# 88.net
KiCad netlist of a schematic drawn in Altium Designer
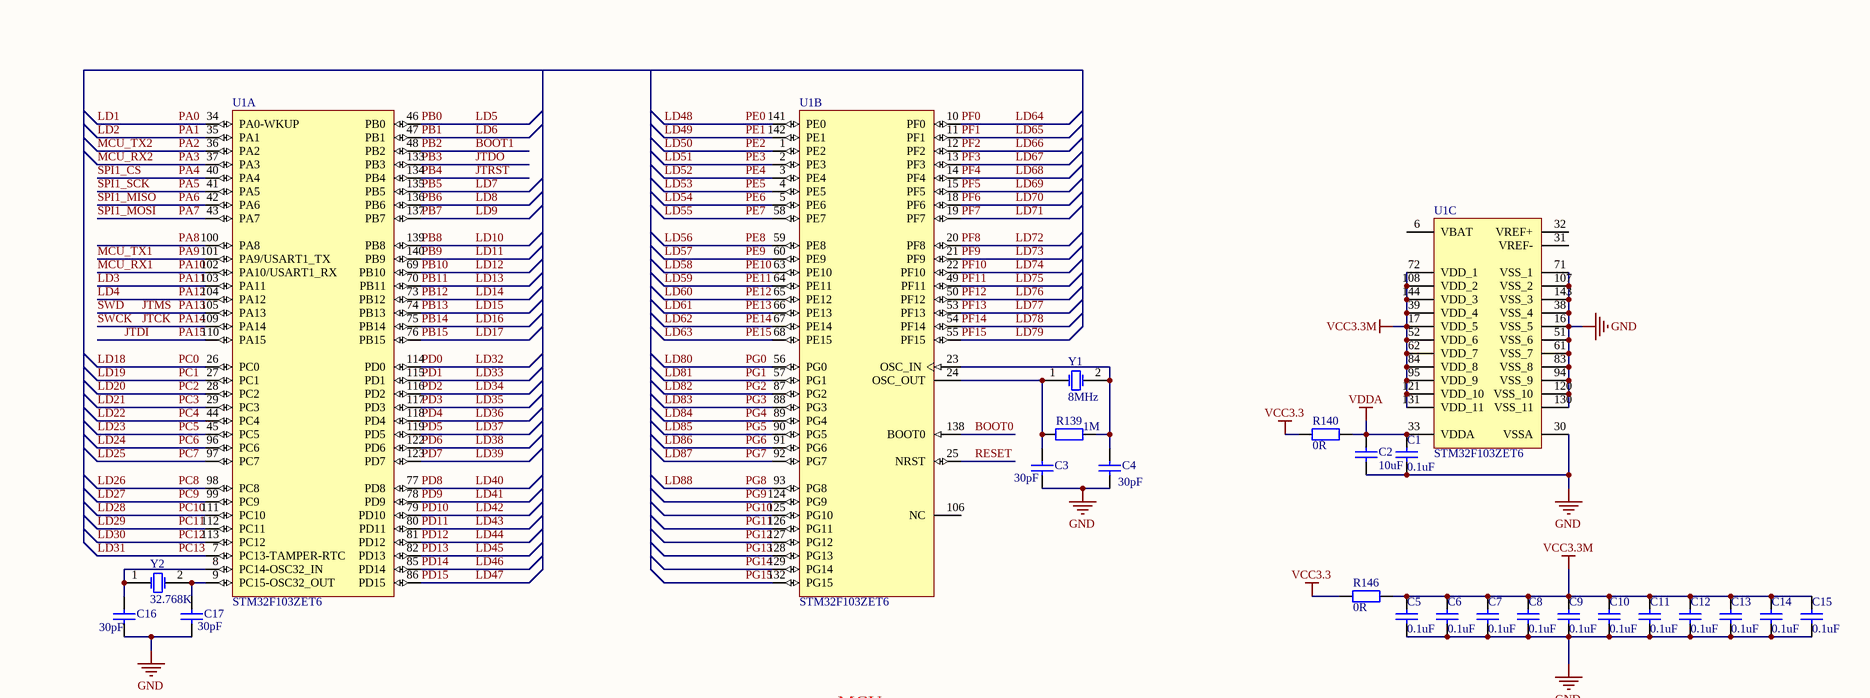
[diagram p0: 88路激光器工程.SchDoc, top left]
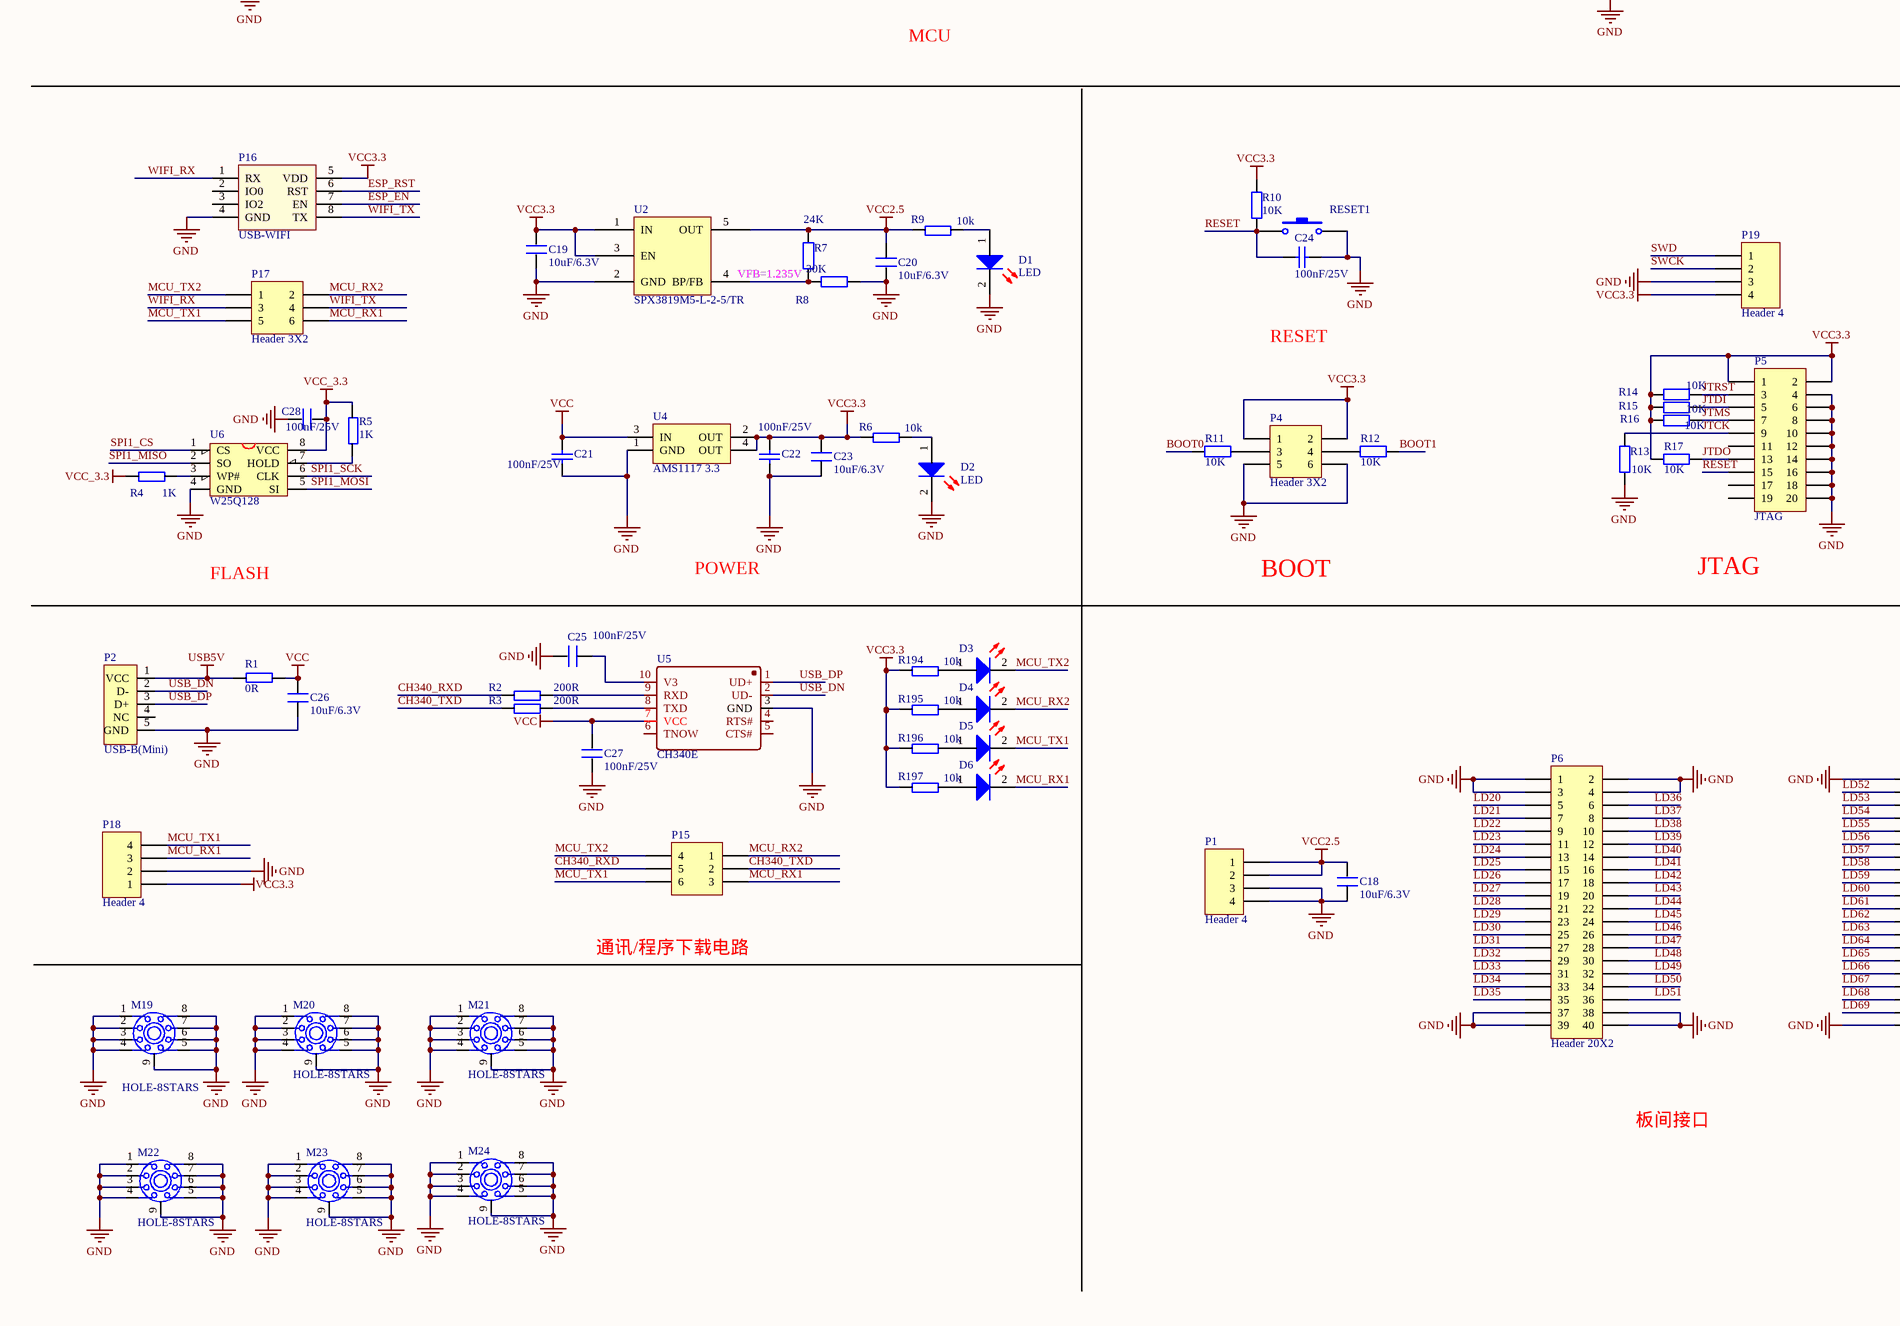
[diagram p1: 88路激光器工程.SchDoc, bottom left]
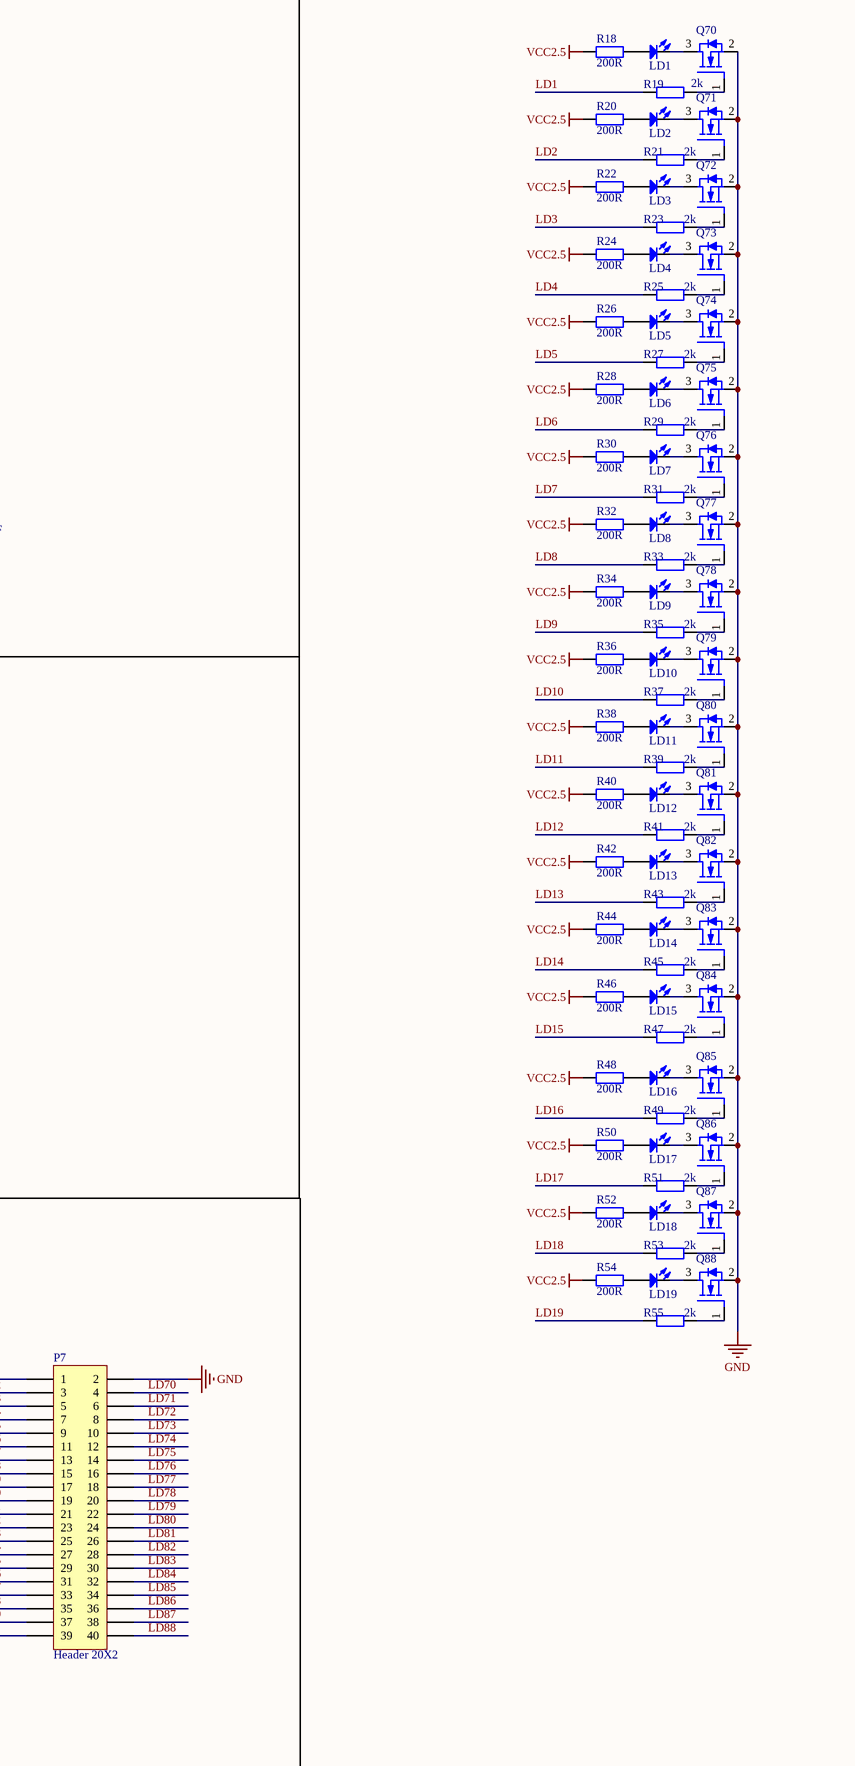
[diagram p2: 88路激光器工程.SchDoc, bottom right]

(export (version "E")
  (design (tool "Eeschema 10.0.6"))
  (components
    (comp (ref "C1")
      (value "0.1uF")
      (footprint "C0805")
      (description "Capacitor")
      (fields (field (name "PUBLISHER") "Altium Limited"))
      (libsource (lib "Miscellaneous Devices") (part "Cap"))
    )
    (comp (ref "C2")
      (value "10uF")
      (footprint "C0805")
      (description "Capacitor")
      (fields (field (name "PUBLISHER") "Altium Limited"))
      (libsource (lib "Miscellaneous Devices") (part "Cap"))
    )
    (comp (ref "C3")
      (value "30pF")
      (footprint "C0805")
      (description "Capacitor")
      (fields (field (name "PUBLISHER") "Altium Limited"))
      (libsource (lib "Miscellaneous Devices") (part "Cap"))
    )
    (comp (ref "C4")
      (value "30pF")
      (footprint "C0805")
      (description "Capacitor")
      (fields (field (name "PUBLISHER") "Altium Limited"))
      (libsource (lib "Miscellaneous Devices") (part "Cap"))
    )
    (comp (ref "C5")
      (value "0.1uF")
      (footprint "C0805")
      (description "Capacitor")
      (fields (field (name "PUBLISHER") "Altium Limited"))
      (libsource (lib "Miscellaneous Devices") (part "Cap"))
    )
    (comp (ref "C6")
      (value "0.1uF")
      (footprint "C0805")
      (description "Capacitor")
      (fields (field (name "PUBLISHER") "Altium Limited"))
      (libsource (lib "Miscellaneous Devices") (part "Cap"))
    )
    (comp (ref "C7")
      (value "0.1uF")
      (footprint "C0805")
      (description "Capacitor")
      (fields (field (name "PUBLISHER") "Altium Limited"))
      (libsource (lib "Miscellaneous Devices") (part "Cap"))
    )
    (comp (ref "C8")
      (value "0.1uF")
      (footprint "C0805")
      (description "Capacitor")
      (fields (field (name "PUBLISHER") "Altium Limited"))
      (libsource (lib "Miscellaneous Devices") (part "Cap"))
    )
    (comp (ref "C9")
      (value "0.1uF")
      (footprint "C0805")
      (description "Capacitor")
      (fields (field (name "PUBLISHER") "Altium Limited"))
      (libsource (lib "Miscellaneous Devices") (part "Cap"))
    )
    (comp (ref "C10")
      (value "0.1uF")
      (footprint "C0805")
      (description "Capacitor")
      (fields (field (name "PUBLISHER") "Altium Limited"))
      (libsource (lib "Miscellaneous Devices") (part "Cap"))
    )
    (comp (ref "C11")
      (value "0.1uF")
      (footprint "C0805")
      (description "Capacitor")
      (fields (field (name "PUBLISHER") "Altium Limited"))
      (libsource (lib "Miscellaneous Devices") (part "Cap"))
    )
    (comp (ref "C12")
      (value "0.1uF")
      (footprint "C0805")
      (description "Capacitor")
      (fields (field (name "PUBLISHER") "Altium Limited"))
      (libsource (lib "Miscellaneous Devices") (part "Cap"))
    )
    (comp (ref "C13")
      (value "0.1uF")
      (footprint "C0805")
      (description "Capacitor")
      (fields (field (name "PUBLISHER") "Altium Limited"))
      (libsource (lib "Miscellaneous Devices") (part "Cap"))
    )
    (comp (ref "C14")
      (value "0.1uF")
      (footprint "C0805")
      (description "Capacitor")
      (fields (field (name "PUBLISHER") "Altium Limited"))
      (libsource (lib "Miscellaneous Devices") (part "Cap"))
    )
    (comp (ref "C15")
      (value "0.1uF")
      (footprint "C0805")
      (description "Capacitor")
      (fields (field (name "PUBLISHER") "Altium Limited"))
      (libsource (lib "Miscellaneous Devices") (part "Cap"))
    )
    (comp (ref "C16")
      (value "30pF")
      (footprint "C0805")
      (description "Capacitor")
      (fields (field (name "PUBLISHER") "Altium Limited"))
      (libsource (lib "Miscellaneous Devices") (part "Cap"))
    )
    (comp (ref "C17")
      (value "30pF")
      (footprint "C0805")
      (description "Capacitor")
      (fields (field (name "PUBLISHER") "Altium Limited"))
      (libsource (lib "Miscellaneous Devices") (part "Cap"))
    )
    (comp (ref "C18")
      (value "10uF/6.3V")
      (footprint "C0805")
      (libsource (lib "Explorer STM32F407封装库2") (part "C"))
    )
    (comp (ref "C19")
      (value "10uF/6.3V")
      (footprint "C0805")
      (libsource (lib "Explorer STM32F407封装库2") (part "C"))
    )
    (comp (ref "C20")
      (value "10uF/6.3V")
      (footprint "C0805")
      (libsource (lib "Explorer STM32F407封装库2") (part "C"))
    )
    (comp (ref "C21")
      (value "100nF/25V")
      (footprint "C0805")
      (description "Capacitor")
      (fields (field (name "PUBLISHER") "Altium Limited"))
      (libsource (lib "Miscellaneous Devices") (part "Cap"))
    )
    (comp (ref "C22")
      (value "100nF/25V")
      (footprint "C0805")
      (description "Capacitor")
      (fields (field (name "PUBLISHER") "Altium Limited"))
      (libsource (lib "Miscellaneous Devices") (part "Cap"))
    )
    (comp (ref "C23")
      (value "10uF/6.3V")
      (footprint "C0805")
      (libsource (lib "Explorer STM32F407封装库2") (part "C"))
    )
    (comp (ref "C24")
      (value "100nF/25V")
      (footprint "C0805")
      (description "Capacitor")
      (fields (field (name "PUBLISHER") "Altium Limited"))
      (libsource (lib "Miscellaneous Devices") (part "Cap"))
    )
    (comp (ref "C25")
      (value "100nF/25V")
      (footprint "C0805")
      (libsource (lib "Explorer STM32F407封装库2") (part "C"))
    )
    (comp (ref "C26")
      (value "10uF/6.3V")
      (footprint "C0805")
      (libsource (lib "Explorer STM32F407封装库2") (part "C"))
    )
    (comp (ref "C27")
      (value "100nF/25V")
      (footprint "C0805")
      (libsource (lib "Explorer STM32F407封装库2") (part "C"))
    )
    (comp (ref "C28")
      (value "100nF/25V")
      (footprint "C0805")
      (libsource (lib "Explorer STM32F407封装库2") (part "C"))
    )
    (comp (ref "D1")
      (value "LED")
      (footprint "LED_0805")
      (description "0603 无色透明 λp=940nm VR=5V VF(typ)=1.2V IF=65mA PD=130mW")
      (libsource (lib "TOF_SCH") (part "LED_IR"))
    )
    (comp (ref "D2")
      (value "LED")
      (footprint "LED_0805")
      (description "0603 无色透明 λp=940nm VR=5V VF(typ)=1.2V IF=65mA PD=130mW")
      (libsource (lib "TOF_SCH") (part "LED_IR"))
    )
    (comp (ref "D3")
      (value "LED")
      (footprint "LED_0805")
      (description "0603 无色透明 λp=940nm VR=5V VF(typ)=1.2V IF=65mA PD=130mW")
      (libsource (lib "TOF_SCH") (part "LED_IR"))
    )
    (comp (ref "D4")
      (value "LED")
      (footprint "LED_0805")
      (description "0603 无色透明 λp=940nm VR=5V VF(typ)=1.2V IF=65mA PD=130mW")
      (libsource (lib "TOF_SCH") (part "LED_IR"))
    )
    (comp (ref "D5")
      (value "LED")
      (footprint "LED_0805")
      (description "0603 无色透明 λp=940nm VR=5V VF(typ)=1.2V IF=65mA PD=130mW")
      (libsource (lib "TOF_SCH") (part "LED_IR"))
    )
    (comp (ref "D6")
      (value "LED")
      (footprint "LED_0805")
      (description "0603 无色透明 λp=940nm VR=5V VF(typ)=1.2V IF=65mA PD=130mW")
      (libsource (lib "TOF_SCH") (part "LED_IR"))
    )
    (comp (ref "LD1") (value "LD") (footprint "LD_3P") (libsource (lib "SchLib1") (part "LD")))
    (comp (ref "LD2") (value "LD") (footprint "LD_3P") (libsource (lib "SchLib1") (part "LD")))
    (comp (ref "LD3") (value "LD") (footprint "LD_3P") (libsource (lib "SchLib1") (part "LD")))
    (comp (ref "LD4") (value "LD") (footprint "LD_3P") (libsource (lib "SchLib1") (part "LD")))
    (comp (ref "LD5") (value "LD") (footprint "LD_3P") (libsource (lib "SchLib1") (part "LD")))
    (comp (ref "LD6") (value "LD") (footprint "LD_3P") (libsource (lib "SchLib1") (part "LD")))
    (comp (ref "LD7") (value "LD") (footprint "LD_3P") (libsource (lib "SchLib1") (part "LD")))
    (comp (ref "LD8") (value "LD") (footprint "LD_3P") (libsource (lib "SchLib1") (part "LD")))
    (comp (ref "LD9") (value "LD") (footprint "LD_3P") (libsource (lib "SchLib1") (part "LD")))
    (comp (ref "LD10") (value "LD") (footprint "LD_3P") (libsource (lib "SchLib1") (part "LD")))
    (comp (ref "LD11") (value "LD") (footprint "LD_3P") (libsource (lib "SchLib1") (part "LD")))
    (comp (ref "LD12") (value "LD") (footprint "LD_3P") (libsource (lib "SchLib1") (part "LD")))
    (comp (ref "LD13") (value "LD") (footprint "LD_3P") (libsource (lib "SchLib1") (part "LD")))
    (comp (ref "LD14") (value "LD") (footprint "LD_3P") (libsource (lib "SchLib1") (part "LD")))
    (comp (ref "LD15") (value "LD") (footprint "LD_3P") (libsource (lib "SchLib1") (part "LD")))
    (comp (ref "LD16") (value "LD") (footprint "LD_3P") (libsource (lib "SchLib1") (part "LD")))
    (comp (ref "LD17") (value "LD") (footprint "LD_3P") (libsource (lib "SchLib1") (part "LD")))
    (comp (ref "LD18") (value "LD") (footprint "LD_3P") (libsource (lib "SchLib1") (part "LD")))
    (comp (ref "LD19") (value "LD") (footprint "LD_3P") (libsource (lib "SchLib1") (part "LD")))
    (comp (ref "M19")
      (value "HOLE-8STARS")
      (footprint "HOLE_3MM")
      (libsource (lib "TOF_SCH") (part "HOLE-8STARS"))
    )
    (comp (ref "M20")
      (value "HOLE-8STARS")
      (footprint "HOLE_3MM")
      (libsource (lib "TOF_SCH") (part "HOLE-8STARS"))
    )
    (comp (ref "M21")
      (value "HOLE-8STARS")
      (footprint "HOLE_3MM")
      (libsource (lib "TOF_SCH") (part "HOLE-8STARS"))
    )
    (comp (ref "M22")
      (value "HOLE-8STARS")
      (footprint "HOLE_3MM")
      (libsource (lib "TOF_SCH") (part "HOLE-8STARS"))
    )
    (comp (ref "M23")
      (value "HOLE-8STARS")
      (footprint "HOLE_3MM")
      (libsource (lib "TOF_SCH") (part "HOLE-8STARS"))
    )
    (comp (ref "M24")
      (value "HOLE-8STARS")
      (footprint "HOLE_3MM")
      (libsource (lib "TOF_SCH") (part "HOLE-8STARS"))
    )
    (comp (ref "P1")
      (value "Header 4")
      (footprint "XH2.54MM_4P_立式")
      (description "Header, 4-Pin")
      (fields (field (name "PUBLISHER") "Altium Limited"))
      (libsource (lib "") (part "Header 4_2"))
    )
    (comp (ref "P2")
      (value "USB-B(Mini)")
      (footprint "MICRO_USB5P_带牛角")
      (libsource (lib "阿波罗STM32F4&F7底板封装库") (part "USB5"))
    )
    (comp (ref "P4")
      (value "Header 3X2")
      (footprint "HDR2X3")
      (description "Header, 3-Pin, Dual row")
      (fields (field (name "PUBLISHER") "Altium Limited"))
      (libsource (lib "Miscellaneous Connectors") (part "Header 3X2"))
    )
    (comp (ref "P5")
      (value "JTAG")
      (footprint "JTAG_2X10P_2.54MM")
      (description "Header, 10-Pin, Dual row")
      (fields (field (name "PUBLISHER") "Altium Limited"))
      (libsource (lib "Miscellaneous Connectors") (part "Header 10X2"))
    )
    (comp (ref "P6")
      (value "Header 20X2")
      (footprint "JATG_2.0mm_2x20P_SMD")
      (description "Header, 20-Pin, Dual row")
      (fields (field (name "PUBLISHER") "Altium Limited"))
      (libsource (lib "Miscellaneous Connectors") (part "Header 20X2"))
    )
    (comp (ref "P7")
      (value "Header 20X2")
      (footprint "JATG_2.0mm_2x20P_SMD")
      (description "Header, 20-Pin, Dual row")
      (fields (field (name "PUBLISHER") "Altium Limited"))
      (libsource (lib "Miscellaneous Connectors") (part "Header 20X2"))
    )
    (comp (ref "P15")
      (value "Header 3X2A")
      (footprint "HDR2X3_CEN")
      (description "Header, 3-Pin, Dual row")
      (fields (field (name "PUBLISHER") "Altium Limited"))
      (libsource (lib "Miscellaneous Connectors") (part "Header 3X2A"))
    )
    (comp (ref "P16")
      (value "USB-WIFI")
      (footprint "UART-WIFI")
      (libsource (lib "Schlib1") (part "USB-WIFI"))
    )
    (comp (ref "P17")
      (value "Header 3X2")
      (footprint "HDR2X3")
      (description "Header, 3-Pin, Dual row")
      (fields (field (name "PUBLISHER") "Altium Limited"))
      (libsource (lib "Miscellaneous Connectors") (part "Header 3X2"))
    )
    (comp (ref "P18")
      (value "Header 4")
      (footprint "HDR1X4")
      (description "Header, 4-Pin")
      (fields (field (name "PUBLISHER") "Altium Limited"))
      (libsource (lib "") (part "Header 4_1"))
    )
    (comp (ref "P19")
      (value "Header 4")
      (footprint "HDR1X4")
      (description "Header, 4-Pin")
      (fields (field (name "PUBLISHER") "Altium Limited"))
      (libsource (lib "Miscellaneous Connectors") (part "Header 4"))
    )
    (comp (ref "Q70") (value "NMOS") (footprint "SOT23-3") (libsource (lib "88路激光器工程") (part "NMOS")))
    (comp (ref "Q71") (value "NMOS") (footprint "SOT23-3") (libsource (lib "88路激光器工程") (part "NMOS")))
    (comp (ref "Q72") (value "NMOS") (footprint "SOT23-3") (libsource (lib "88路激光器工程") (part "NMOS")))
    (comp (ref "Q73") (value "NMOS") (footprint "SOT23-3") (libsource (lib "88路激光器工程") (part "NMOS")))
    (comp (ref "Q74") (value "NMOS") (footprint "SOT23-3") (libsource (lib "88路激光器工程") (part "NMOS")))
    (comp (ref "Q75") (value "NMOS") (footprint "SOT23-3") (libsource (lib "88路激光器工程") (part "NMOS")))
    (comp (ref "Q76") (value "NMOS") (footprint "SOT23-3") (libsource (lib "88路激光器工程") (part "NMOS")))
    (comp (ref "Q77") (value "NMOS") (footprint "SOT23-3") (libsource (lib "88路激光器工程") (part "NMOS")))
    (comp (ref "Q78") (value "NMOS") (footprint "SOT23-3") (libsource (lib "88路激光器工程") (part "NMOS")))
    (comp (ref "Q79") (value "NMOS") (footprint "SOT23-3") (libsource (lib "88路激光器工程") (part "NMOS")))
    (comp (ref "Q80") (value "NMOS") (footprint "SOT23-3") (libsource (lib "88路激光器工程") (part "NMOS")))
    (comp (ref "Q81") (value "NMOS") (footprint "SOT23-3") (libsource (lib "88路激光器工程") (part "NMOS")))
    (comp (ref "Q82") (value "NMOS") (footprint "SOT23-3") (libsource (lib "88路激光器工程") (part "NMOS")))
    (comp (ref "Q83") (value "NMOS") (footprint "SOT23-3") (libsource (lib "88路激光器工程") (part "NMOS")))
    (comp (ref "Q84") (value "NMOS") (footprint "SOT23-3") (libsource (lib "88路激光器工程") (part "NMOS")))
    (comp (ref "Q85") (value "NMOS") (footprint "SOT23-3") (libsource (lib "88路激光器工程") (part "NMOS")))
    (comp (ref "Q86") (value "NMOS") (footprint "SOT23-3") (libsource (lib "88路激光器工程") (part "NMOS")))
    (comp (ref "Q87") (value "NMOS") (footprint "SOT23-3") (libsource (lib "88路激光器工程") (part "NMOS")))
    (comp (ref "Q88") (value "NMOS") (footprint "SOT23-3") (libsource (lib "88路激光器工程") (part "NMOS")))
    (comp (ref "R1") (value "0R") (footprint "R0805") (libsource (lib "Explorer STM32F407封装库2") (part "R")))
    (comp (ref "R2") (value "200R") (footprint "R0805") (libsource (lib "Explorer STM32F407封装库2") (part "R")))
    (comp (ref "R3") (value "200R") (footprint "R0805") (libsource (lib "Explorer STM32F407封装库2") (part "R")))
    (comp (ref "R4") (value "1K") (footprint "R0805") (libsource (lib "Explorer STM32F407封装库2") (part "R")))
    (comp (ref "R5") (value "1K") (footprint "R0805") (libsource (lib "Explorer STM32F407封装库2") (part "R")))
    (comp (ref "R6") (value "10k") (footprint "R0805") (libsource (lib "Explorer STM32F407封装库2") (part "R")))
    (comp (ref "R7")
      (value "24K")
      (footprint "R0805")
      (description "Resistor")
      (fields (field (name "PUBLISHER") "Altium Limited"))
      (libsource (lib "") (part "Res2_2"))
    )
    (comp (ref "R8")
      (value "30K")
      (footprint "R0805")
      (description "Resistor")
      (fields (field (name "PUBLISHER") "Altium Limited"))
      (libsource (lib "Miscellaneous Devices") (part "Res2"))
    )
    (comp (ref "R9") (value "10k") (footprint "R0805") (libsource (lib "Explorer STM32F407封装库2") (part "R")))
    (comp (ref "R10")
      (value "10K")
      (footprint "R0805")
      (description "Resistor")
      (fields (field (name "PUBLISHER") "Altium Limited"))
      (libsource (lib "") (part "Res2_2"))
    )
    (comp (ref "R11")
      (value "10K")
      (footprint "R0805")
      (description "Resistor")
      (fields (field (name "PUBLISHER") "Altium Limited"))
      (libsource (lib "") (part "Res2_1"))
    )
    (comp (ref "R12")
      (value "10K")
      (footprint "R0805")
      (description "Resistor")
      (fields (field (name "PUBLISHER") "Altium Limited"))
      (libsource (lib "") (part "Res2_1"))
    )
    (comp (ref "R13")
      (value "10K")
      (footprint "R0805")
      (description "Resistor")
      (fields (field (name "PUBLISHER") "Altium Limited"))
      (libsource (lib "") (part "Res2_2"))
    )
    (comp (ref "R14")
      (value "10K")
      (footprint "R0805")
      (description "Resistor")
      (fields (field (name "PUBLISHER") "Altium Limited"))
      (libsource (lib "") (part "Res2_1"))
    )
    (comp (ref "R15")
      (value "10K")
      (footprint "R0805")
      (description "Resistor")
      (fields (field (name "PUBLISHER") "Altium Limited"))
      (libsource (lib "") (part "Res2_1"))
    )
    (comp (ref "R16")
      (value "10K")
      (footprint "R0805")
      (description "Resistor")
      (fields (field (name "PUBLISHER") "Altium Limited"))
      (libsource (lib "") (part "Res2_1"))
    )
    (comp (ref "R17")
      (value "10K")
      (footprint "R0805")
      (description "Resistor")
      (fields (field (name "PUBLISHER") "Altium Limited"))
      (libsource (lib "") (part "Res2_1"))
    )
    (comp (ref "R18")
      (value "200R")
      (footprint "R0805")
      (description "Resistor")
      (fields (field (name "PUBLISHER") "Altium Limited"))
      (libsource (lib "Miscellaneous Devices") (part "Res2"))
    )
    (comp (ref "R19")
      (value "2k")
      (footprint "R0805")
      (description "Resistor")
      (fields (field (name "PUBLISHER") "Altium Limited"))
      (libsource (lib "Miscellaneous Devices") (part "Res2"))
    )
    (comp (ref "R20")
      (value "200R")
      (footprint "R0805")
      (description "Resistor")
      (fields (field (name "PUBLISHER") "Altium Limited"))
      (libsource (lib "Miscellaneous Devices") (part "Res2"))
    )
    (comp (ref "R21")
      (value "2k")
      (footprint "R0805")
      (description "Resistor")
      (fields (field (name "PUBLISHER") "Altium Limited"))
      (libsource (lib "Miscellaneous Devices") (part "Res2"))
    )
    (comp (ref "R22")
      (value "200R")
      (footprint "R0805")
      (description "Resistor")
      (fields (field (name "PUBLISHER") "Altium Limited"))
      (libsource (lib "Miscellaneous Devices") (part "Res2"))
    )
    (comp (ref "R23")
      (value "2k")
      (footprint "R0805")
      (description "Resistor")
      (fields (field (name "PUBLISHER") "Altium Limited"))
      (libsource (lib "Miscellaneous Devices") (part "Res2"))
    )
    (comp (ref "R24")
      (value "200R")
      (footprint "R0805")
      (description "Resistor")
      (fields (field (name "PUBLISHER") "Altium Limited"))
      (libsource (lib "Miscellaneous Devices") (part "Res2"))
    )
    (comp (ref "R25")
      (value "2k")
      (footprint "R0805")
      (description "Resistor")
      (fields (field (name "PUBLISHER") "Altium Limited"))
      (libsource (lib "Miscellaneous Devices") (part "Res2"))
    )
    (comp (ref "R26")
      (value "200R")
      (footprint "R0805")
      (description "Resistor")
      (fields (field (name "PUBLISHER") "Altium Limited"))
      (libsource (lib "Miscellaneous Devices") (part "Res2"))
    )
    (comp (ref "R27")
      (value "2k")
      (footprint "R0805")
      (description "Resistor")
      (fields (field (name "PUBLISHER") "Altium Limited"))
      (libsource (lib "Miscellaneous Devices") (part "Res2"))
    )
    (comp (ref "R28")
      (value "200R")
      (footprint "R0805")
      (description "Resistor")
      (fields (field (name "PUBLISHER") "Altium Limited"))
      (libsource (lib "Miscellaneous Devices") (part "Res2"))
    )
    (comp (ref "R29")
      (value "2k")
      (footprint "R0805")
      (description "Resistor")
      (fields (field (name "PUBLISHER") "Altium Limited"))
      (libsource (lib "Miscellaneous Devices") (part "Res2"))
    )
    (comp (ref "R30")
      (value "200R")
      (footprint "R0805")
      (description "Resistor")
      (fields (field (name "PUBLISHER") "Altium Limited"))
      (libsource (lib "Miscellaneous Devices") (part "Res2"))
    )
    (comp (ref "R31")
      (value "2k")
      (footprint "R0805")
      (description "Resistor")
      (fields (field (name "PUBLISHER") "Altium Limited"))
      (libsource (lib "Miscellaneous Devices") (part "Res2"))
    )
    (comp (ref "R32")
      (value "200R")
      (footprint "R0805")
      (description "Resistor")
      (fields (field (name "PUBLISHER") "Altium Limited"))
      (libsource (lib "Miscellaneous Devices") (part "Res2"))
    )
    (comp (ref "R33")
      (value "2k")
      (footprint "R0805")
      (description "Resistor")
      (fields (field (name "PUBLISHER") "Altium Limited"))
      (libsource (lib "Miscellaneous Devices") (part "Res2"))
    )
    (comp (ref "R34")
      (value "200R")
      (footprint "R0805")
      (description "Resistor")
      (fields (field (name "PUBLISHER") "Altium Limited"))
      (libsource (lib "Miscellaneous Devices") (part "Res2"))
    )
    (comp (ref "R35")
      (value "2k")
      (footprint "R0805")
      (description "Resistor")
      (fields (field (name "PUBLISHER") "Altium Limited"))
      (libsource (lib "Miscellaneous Devices") (part "Res2"))
    )
    (comp (ref "R36")
      (value "200R")
      (footprint "R0805")
      (description "Resistor")
      (fields (field (name "PUBLISHER") "Altium Limited"))
      (libsource (lib "Miscellaneous Devices") (part "Res2"))
    )
    (comp (ref "R37")
      (value "2k")
      (footprint "R0805")
      (description "Resistor")
      (fields (field (name "PUBLISHER") "Altium Limited"))
      (libsource (lib "Miscellaneous Devices") (part "Res2"))
    )
    (comp (ref "R38")
      (value "200R")
      (footprint "R0805")
      (description "Resistor")
      (fields (field (name "PUBLISHER") "Altium Limited"))
      (libsource (lib "Miscellaneous Devices") (part "Res2"))
    )
    (comp (ref "R39")
      (value "2k")
      (footprint "R0805")
      (description "Resistor")
      (fields (field (name "PUBLISHER") "Altium Limited"))
      (libsource (lib "Miscellaneous Devices") (part "Res2"))
    )
    (comp (ref "R40")
      (value "200R")
      (footprint "R0805")
      (description "Resistor")
      (fields (field (name "PUBLISHER") "Altium Limited"))
      (libsource (lib "Miscellaneous Devices") (part "Res2"))
    )
    (comp (ref "R41")
      (value "2k")
      (footprint "R0805")
      (description "Resistor")
      (fields (field (name "PUBLISHER") "Altium Limited"))
      (libsource (lib "Miscellaneous Devices") (part "Res2"))
    )
    (comp (ref "R42")
      (value "200R")
      (footprint "R0805")
      (description "Resistor")
      (fields (field (name "PUBLISHER") "Altium Limited"))
      (libsource (lib "Miscellaneous Devices") (part "Res2"))
    )
    (comp (ref "R43")
      (value "2k")
      (footprint "R0805")
      (description "Resistor")
      (fields (field (name "PUBLISHER") "Altium Limited"))
      (libsource (lib "Miscellaneous Devices") (part "Res2"))
    )
    (comp (ref "R44")
      (value "200R")
      (footprint "R0805")
      (description "Resistor")
      (fields (field (name "PUBLISHER") "Altium Limited"))
      (libsource (lib "Miscellaneous Devices") (part "Res2"))
    )
    (comp (ref "R45")
      (value "2k")
      (footprint "R0805")
      (description "Resistor")
      (fields (field (name "PUBLISHER") "Altium Limited"))
      (libsource (lib "Miscellaneous Devices") (part "Res2"))
    )
    (comp (ref "R46")
      (value "200R")
      (footprint "R0805")
      (description "Resistor")
      (fields (field (name "PUBLISHER") "Altium Limited"))
      (libsource (lib "Miscellaneous Devices") (part "Res2"))
    )
    (comp (ref "R47")
      (value "2k")
      (footprint "R0805")
      (description "Resistor")
      (fields (field (name "PUBLISHER") "Altium Limited"))
      (libsource (lib "Miscellaneous Devices") (part "Res2"))
    )
    (comp (ref "R48")
      (value "200R")
      (footprint "R0805")
      (description "Resistor")
      (fields (field (name "PUBLISHER") "Altium Limited"))
      (libsource (lib "Miscellaneous Devices") (part "Res2"))
    )
    (comp (ref "R49")
      (value "2k")
      (footprint "R0805")
      (description "Resistor")
      (fields (field (name "PUBLISHER") "Altium Limited"))
      (libsource (lib "Miscellaneous Devices") (part "Res2"))
    )
    (comp (ref "R50")
      (value "200R")
      (footprint "R0805")
      (description "Resistor")
      (fields (field (name "PUBLISHER") "Altium Limited"))
      (libsource (lib "Miscellaneous Devices") (part "Res2"))
    )
    (comp (ref "R51")
      (value "2k")
      (footprint "R0805")
      (description "Resistor")
      (fields (field (name "PUBLISHER") "Altium Limited"))
      (libsource (lib "Miscellaneous Devices") (part "Res2"))
    )
    (comp (ref "R52")
      (value "200R")
      (footprint "R0805")
      (description "Resistor")
      (fields (field (name "PUBLISHER") "Altium Limited"))
      (libsource (lib "Miscellaneous Devices") (part "Res2"))
    )
    (comp (ref "R53")
      (value "2k")
      (footprint "R0805")
      (description "Resistor")
      (fields (field (name "PUBLISHER") "Altium Limited"))
      (libsource (lib "Miscellaneous Devices") (part "Res2"))
    )
    (comp (ref "R54")
      (value "200R")
      (footprint "R0805")
      (description "Resistor")
      (fields (field (name "PUBLISHER") "Altium Limited"))
      (libsource (lib "Miscellaneous Devices") (part "Res2"))
    )
    (comp (ref "R55")
      (value "2k")
      (footprint "R0805")
      (description "Resistor")
      (fields (field (name "PUBLISHER") "Altium Limited"))
      (libsource (lib "Miscellaneous Devices") (part "Res2"))
    )
    (comp (ref "R139")
      (value "1M")
      (footprint "R0805")
      (description "Resistor")
      (fields (field (name "PUBLISHER") "Altium Limited"))
      (libsource (lib "") (part "Res2_1"))
    )
    (comp (ref "R140")
      (value "0R")
      (footprint "R0805")
      (description "Resistor")
      (fields (field (name "PUBLISHER") "Altium Limited"))
      (libsource (lib "") (part "Res2_1"))
    )
    (comp (ref "R146")
      (value "0R")
      (footprint "R0805")
      (description "Resistor")
      (fields (field (name "PUBLISHER") "Altium Limited"))
      (libsource (lib "") (part "Res2_1"))
    )
    (comp (ref "R194")
      (value "10k")
      (footprint "R0805")
      (libsource (lib "Explorer STM32F407封装库2") (part "R"))
    )
    (comp (ref "R195")
      (value "10k")
      (footprint "R0805")
      (libsource (lib "Explorer STM32F407封装库2") (part "R"))
    )
    (comp (ref "R196")
      (value "10k")
      (footprint "R0805")
      (libsource (lib "Explorer STM32F407封装库2") (part "R"))
    )
    (comp (ref "R197")
      (value "10k")
      (footprint "R0805")
      (libsource (lib "Explorer STM32F407封装库2") (part "R"))
    )
    (comp (ref "RESET1")
      (value "SW-PB")
      (footprint "KEY_PB_6X6X5")
      (description "Switch")
      (fields (field (name "PUBLISHER") "Altium Limited"))
      (libsource (lib "Miscellaneous Devices") (part "SW-PB"))
    )
    (comp (ref "U1")
      (value "STM32F103ZET6")
      (footprint "LQFP-144")
      (libsource (lib "SchLib1") (part "STM32F103ZET6"))
    )
    (comp (ref "U2")
      (value "SPX3819M5-L-2-5/TR")
      (footprint "SOT23-5")
      (description "500mA Low-Noise LDO Voltage Regulator")
      (libsource (lib "TOF_SCH") (part "SPX3819M5-L-1-2/TR"))
    )
    (comp (ref "U4")
      (value "AMS1117 3.3")
      (footprint "SOT-223")
      (description "800mA and 1A Low Dropout Positive Regulator 2.85V, 3.3V, 5V, and Adjustable")
      (fields (field (name "PUBLISHER") "Altium Limited"))
      (libsource (lib "BB Power Mgt Voltage Regulator") (part "REG1117-3.3"))
    )
    (comp (ref "U5") (value "CH340E") (footprint "MSOP-10") (libsource (lib "IWatch") (part "CH340E")))
    (comp (ref "U6")
      (value "W25Q128")
      (footprint "SOIC-8_208MIL")
      (description "W25X16;SST25VF016;MX25L1605")
      (libsource (lib "Explorer STM32F407封装库2") (part "W25X16"))
    )
    (comp (ref "Y1")
      (value "8MHz")
      (footprint "HC-49S")
      (description "Crystal Oscillator")
      (fields (field (name "PUBLISHER") "Altium Limited"))
      (libsource (lib "Miscellaneous Devices") (part "XTAL"))
    )
    (comp (ref "Y2")
      (value "32.768K")
      (footprint "XTAL_32KHZ_TH__2P")
      (description "Crystal Oscillator")
      (fields (field (name "PUBLISHER") "Altium Limited"))
      (libsource (lib "Miscellaneous Devices") (part "XTAL"))
    )
  )
  (nets
    (net (code "1") (name "/BOOT0") (class "Default")
      (node (ref "R11") (pin "1") (pinfunction "1_1") (pintype "passive"))
      (node (ref "U1") (pin "138") (pinfunction "BOOT0_138") (pintype "input"))
    )
    (net (code "2") (name "/BOOT1") (class "Default")
      (node (ref "R12") (pin "2") (pinfunction "2_2") (pintype "passive"))
      (node (ref "U1") (pin "48") (pinfunction "PB2_48") (pintype "bidirectional"))
    )
    (net (code "3") (name "/CH340_RXD") (class "Default")
      (node (ref "P15") (pin "5") (pinfunction "5_5") (pintype "passive"))
      (node (ref "R2") (pin "1") (pintype "passive"))
    )
    (net (code "4") (name "/CH340_TXD") (class "Default")
      (node (ref "P15") (pin "2") (pinfunction "2_2") (pintype "passive"))
      (node (ref "R3") (pin "1") (pintype "passive"))
    )
    (net (code "5") (name "/ESP_EN") (class "Default")
      (node (ref "P16") (pin "7") (pinfunction "EN_7") (pintype "passive"))
    )
    (net (code "6") (name "/ESP_RST") (class "Default")
      (node (ref "P16") (pin "6") (pinfunction "RST_6") (pintype "passive"))
    )
    (net (code "7") (name "/JTCK") (class "Default")
      (node (ref "P19") (pin "2") (pinfunction "2_2") (pintype "passive"))
      (node (ref "P5") (pin "9") (pinfunction "9_9") (pintype "passive"))
      (node (ref "R13") (pin "2") (pinfunction "2_2") (pintype "passive"))
      (node (ref "U1") (pin "109") (pinfunction "PA14_109") (pintype "bidirectional"))
    )
    (net (code "8") (name "/JTDI") (class "Default")
      (node (ref "P5") (pin "5") (pinfunction "5_5") (pintype "passive"))
      (node (ref "R15") (pin "2") (pinfunction "2_2") (pintype "passive"))
      (node (ref "U1") (pin "110") (pinfunction "PA15_110") (pintype "bidirectional"))
    )
    (net (code "9") (name "/JTDO") (class "Default")
      (node (ref "P5") (pin "13") (pinfunction "13_13") (pintype "passive"))
      (node (ref "R17") (pin "2") (pinfunction "2_2") (pintype "passive"))
      (node (ref "U1") (pin "133") (pinfunction "PB3_133") (pintype "bidirectional"))
    )
    (net (code "10") (name "/JTMS") (class "Default")
      (node (ref "P19") (pin "1") (pinfunction "1_1") (pintype "passive"))
      (node (ref "P5") (pin "7") (pinfunction "7_7") (pintype "passive"))
      (node (ref "R16") (pin "2") (pinfunction "2_2") (pintype "passive"))
      (node (ref "U1") (pin "105") (pinfunction "PA13_105") (pintype "bidirectional"))
    )
    (net (code "11") (name "/JTRST") (class "Default")
      (node (ref "P5") (pin "3") (pinfunction "3_3") (pintype "passive"))
      (node (ref "R14") (pin "2") (pinfunction "2_2") (pintype "passive"))
      (node (ref "U1") (pin "134") (pinfunction "PB4_134") (pintype "bidirectional"))
    )
    (net (code "12") (name "/LD1") (class "Default")
      (node (ref "R19") (pin "2") (pinfunction "2_2") (pintype "passive"))
      (node (ref "U1") (pin "34") (pinfunction "PA0-WKUP_34") (pintype "bidirectional"))
    )
    (net (code "13") (name "/LD2") (class "Default")
      (node (ref "R21") (pin "2") (pinfunction "2_2") (pintype "passive"))
      (node (ref "U1") (pin "35") (pinfunction "PA1_35") (pintype "bidirectional"))
    )
    (net (code "14") (name "/LD3") (class "Default")
      (node (ref "R23") (pin "2") (pinfunction "2_2") (pintype "passive"))
      (node (ref "U1") (pin "103") (pinfunction "PA11_103") (pintype "bidirectional"))
    )
    (net (code "15") (name "/LD4") (class "Default")
      (node (ref "R25") (pin "2") (pinfunction "2_2") (pintype "passive"))
      (node (ref "U1") (pin "104") (pinfunction "PA12_104") (pintype "bidirectional"))
    )
    (net (code "16") (name "/LD5") (class "Default")
      (node (ref "R27") (pin "2") (pinfunction "2_2") (pintype "passive"))
      (node (ref "U1") (pin "46") (pinfunction "PB0_46") (pintype "bidirectional"))
    )
    (net (code "17") (name "/LD6") (class "Default")
      (node (ref "R29") (pin "2") (pinfunction "2_2") (pintype "passive"))
      (node (ref "U1") (pin "47") (pinfunction "PB1_47") (pintype "bidirectional"))
    )
    (net (code "18") (name "/LD7") (class "Default")
      (node (ref "R31") (pin "2") (pinfunction "2_2") (pintype "passive"))
      (node (ref "U1") (pin "135") (pinfunction "PB5_135") (pintype "bidirectional"))
    )
    (net (code "19") (name "/LD8") (class "Default")
      (node (ref "R33") (pin "2") (pinfunction "2_2") (pintype "passive"))
      (node (ref "U1") (pin "136") (pinfunction "PB6_136") (pintype "bidirectional"))
    )
    (net (code "20") (name "/LD9") (class "Default")
      (node (ref "R35") (pin "2") (pinfunction "2_2") (pintype "passive"))
      (node (ref "U1") (pin "137") (pinfunction "PB7_137") (pintype "bidirectional"))
    )
    (net (code "21") (name "/LD10") (class "Default")
      (node (ref "R37") (pin "2") (pinfunction "2_2") (pintype "passive"))
      (node (ref "U1") (pin "139") (pinfunction "PB8_139") (pintype "bidirectional"))
    )
    (net (code "22") (name "/LD11") (class "Default")
      (node (ref "R39") (pin "2") (pinfunction "2_2") (pintype "passive"))
      (node (ref "U1") (pin "140") (pinfunction "PB9_140") (pintype "bidirectional"))
    )
    (net (code "23") (name "/LD12") (class "Default")
      (node (ref "R41") (pin "2") (pinfunction "2_2") (pintype "passive"))
      (node (ref "U1") (pin "69") (pinfunction "PB10_69") (pintype "bidirectional"))
    )
    (net (code "24") (name "/LD13") (class "Default")
      (node (ref "R43") (pin "2") (pinfunction "2_2") (pintype "passive"))
      (node (ref "U1") (pin "70") (pinfunction "PB11_70") (pintype "bidirectional"))
    )
    (net (code "25") (name "/LD14") (class "Default")
      (node (ref "R45") (pin "2") (pinfunction "2_2") (pintype "passive"))
      (node (ref "U1") (pin "73") (pinfunction "PB12_73") (pintype "bidirectional"))
    )
    (net (code "26") (name "/LD15") (class "Default")
      (node (ref "R47") (pin "2") (pinfunction "2_2") (pintype "passive"))
      (node (ref "U1") (pin "74") (pinfunction "PB13_74") (pintype "bidirectional"))
    )
    (net (code "27") (name "/LD16") (class "Default")
      (node (ref "R49") (pin "2") (pinfunction "2_2") (pintype "passive"))
      (node (ref "U1") (pin "75") (pinfunction "PB14_75") (pintype "bidirectional"))
    )
    (net (code "28") (name "/LD17") (class "Default")
      (node (ref "R51") (pin "2") (pinfunction "2_2") (pintype "passive"))
      (node (ref "U1") (pin "76") (pinfunction "PB15_76") (pintype "bidirectional"))
    )
    (net (code "29") (name "/LD18") (class "Default")
      (node (ref "R53") (pin "2") (pinfunction "2_2") (pintype "passive"))
      (node (ref "U1") (pin "26") (pinfunction "PC0_26") (pintype "bidirectional"))
    )
    (net (code "30") (name "/LD19") (class "Default")
      (node (ref "R55") (pin "2") (pinfunction "2_2") (pintype "passive"))
      (node (ref "U1") (pin "27") (pinfunction "PC1_27") (pintype "bidirectional"))
    )
    (net (code "31") (name "/LD20") (class "Default")
      (node (ref "P6") (pin "5") (pinfunction "5_5") (pintype "passive"))
      (node (ref "U1") (pin "28") (pinfunction "PC2_28") (pintype "bidirectional"))
    )
    (net (code "32") (name "/LD21") (class "Default")
      (node (ref "P6") (pin "7") (pinfunction "7_7") (pintype "passive"))
      (node (ref "U1") (pin "29") (pinfunction "PC3_29") (pintype "bidirectional"))
    )
    (net (code "33") (name "/LD22") (class "Default")
      (node (ref "P6") (pin "9") (pinfunction "9_9") (pintype "passive"))
      (node (ref "U1") (pin "44") (pinfunction "PC4_44") (pintype "bidirectional"))
    )
    (net (code "34") (name "/LD23") (class "Default")
      (node (ref "P6") (pin "11") (pinfunction "11_11") (pintype "passive"))
      (node (ref "U1") (pin "45") (pinfunction "PC5_45") (pintype "bidirectional"))
    )
    (net (code "35") (name "/LD24") (class "Default")
      (node (ref "P6") (pin "13") (pinfunction "13_13") (pintype "passive"))
      (node (ref "U1") (pin "96") (pinfunction "PC6_96") (pintype "bidirectional"))
    )
    (net (code "36") (name "/LD25") (class "Default")
      (node (ref "P6") (pin "15") (pinfunction "15_15") (pintype "passive"))
      (node (ref "U1") (pin "97") (pinfunction "PC7_97") (pintype "bidirectional"))
    )
    (net (code "37") (name "/LD26") (class "Default")
      (node (ref "P6") (pin "17") (pinfunction "17_17") (pintype "passive"))
      (node (ref "U1") (pin "98") (pinfunction "PC8_98") (pintype "bidirectional"))
    )
    (net (code "38") (name "/LD27") (class "Default")
      (node (ref "P6") (pin "19") (pinfunction "19_19") (pintype "passive"))
      (node (ref "U1") (pin "99") (pinfunction "PC9_99") (pintype "bidirectional"))
    )
    (net (code "39") (name "/LD28") (class "Default")
      (node (ref "P6") (pin "21") (pinfunction "21_21") (pintype "passive"))
      (node (ref "U1") (pin "111") (pinfunction "PC10_111") (pintype "bidirectional"))
    )
    (net (code "40") (name "/LD29") (class "Default")
      (node (ref "P6") (pin "23") (pinfunction "23_23") (pintype "passive"))
      (node (ref "U1") (pin "112") (pinfunction "PC11_112") (pintype "bidirectional"))
    )
    (net (code "41") (name "/LD30") (class "Default")
      (node (ref "P6") (pin "25") (pinfunction "25_25") (pintype "passive"))
      (node (ref "U1") (pin "113") (pinfunction "PC12_113") (pintype "bidirectional"))
    )
    (net (code "42") (name "/LD31") (class "Default")
      (node (ref "P6") (pin "27") (pinfunction "27_27") (pintype "passive"))
      (node (ref "U1") (pin "7") (pinfunction "PC13-TAMPER-RTC_7") (pintype "bidirectional"))
    )
    (net (code "43") (name "/LD32") (class "Default")
      (node (ref "P6") (pin "29") (pinfunction "29_29") (pintype "passive"))
      (node (ref "U1") (pin "114") (pinfunction "PD0_114") (pintype "bidirectional"))
    )
    (net (code "44") (name "/LD33") (class "Default")
      (node (ref "P6") (pin "31") (pinfunction "31_31") (pintype "passive"))
      (node (ref "U1") (pin "115") (pinfunction "PD1_115") (pintype "bidirectional"))
    )
    (net (code "45") (name "/LD34") (class "Default")
      (node (ref "P6") (pin "33") (pinfunction "33_33") (pintype "passive"))
      (node (ref "U1") (pin "116") (pinfunction "PD2_116") (pintype "bidirectional"))
    )
    (net (code "46") (name "/LD35") (class "Default")
      (node (ref "P6") (pin "35") (pinfunction "35_35") (pintype "passive"))
      (node (ref "U1") (pin "117") (pinfunction "PD3_117") (pintype "bidirectional"))
    )
    (net (code "47") (name "/LD36") (class "Default")
      (node (ref "P6") (pin "6") (pinfunction "6_6") (pintype "passive"))
      (node (ref "U1") (pin "118") (pinfunction "PD4_118") (pintype "bidirectional"))
    )
    (net (code "48") (name "/LD37") (class "Default")
      (node (ref "P6") (pin "8") (pinfunction "8_8") (pintype "passive"))
      (node (ref "U1") (pin "119") (pinfunction "PD5_119") (pintype "bidirectional"))
    )
    (net (code "49") (name "/LD38") (class "Default")
      (node (ref "P6") (pin "10") (pinfunction "10_10") (pintype "passive"))
      (node (ref "U1") (pin "122") (pinfunction "PD6_122") (pintype "bidirectional"))
    )
    (net (code "50") (name "/LD39") (class "Default")
      (node (ref "P6") (pin "12") (pinfunction "12_12") (pintype "passive"))
      (node (ref "U1") (pin "123") (pinfunction "PD7_123") (pintype "bidirectional"))
    )
    (net (code "51") (name "/LD40") (class "Default")
      (node (ref "P6") (pin "14") (pinfunction "14_14") (pintype "passive"))
      (node (ref "U1") (pin "77") (pinfunction "PD8_77") (pintype "bidirectional"))
    )
    (net (code "52") (name "/LD41") (class "Default")
      (node (ref "P6") (pin "16") (pinfunction "16_16") (pintype "passive"))
      (node (ref "U1") (pin "78") (pinfunction "PD9_78") (pintype "bidirectional"))
    )
    (net (code "53") (name "/LD42") (class "Default")
      (node (ref "P6") (pin "18") (pinfunction "18_18") (pintype "passive"))
      (node (ref "U1") (pin "79") (pinfunction "PD10_79") (pintype "bidirectional"))
    )
    (net (code "54") (name "/LD43") (class "Default")
      (node (ref "P6") (pin "20") (pinfunction "20_20") (pintype "passive"))
      (node (ref "U1") (pin "80") (pinfunction "PD11_80") (pintype "bidirectional"))
    )
    (net (code "55") (name "/LD44") (class "Default")
      (node (ref "P6") (pin "22") (pinfunction "22_22") (pintype "passive"))
      (node (ref "U1") (pin "81") (pinfunction "PD12_81") (pintype "bidirectional"))
    )
    (net (code "56") (name "/LD45") (class "Default")
      (node (ref "P6") (pin "24") (pinfunction "24_24") (pintype "passive"))
      (node (ref "U1") (pin "82") (pinfunction "PD13_82") (pintype "bidirectional"))
    )
    (net (code "57") (name "/LD46") (class "Default")
      (node (ref "P6") (pin "26") (pinfunction "26_26") (pintype "passive"))
      (node (ref "U1") (pin "85") (pinfunction "PD14_85") (pintype "bidirectional"))
    )
    (net (code "58") (name "/LD47") (class "Default")
      (node (ref "P6") (pin "28") (pinfunction "28_28") (pintype "passive"))
      (node (ref "U1") (pin "86") (pinfunction "PD15_86") (pintype "bidirectional"))
    )
    (net (code "59") (name "/LD48") (class "Default")
      (node (ref "P6") (pin "30") (pinfunction "30_30") (pintype "passive"))
      (node (ref "U1") (pin "141") (pinfunction "PE0_141") (pintype "bidirectional"))
    )
    (net (code "60") (name "/LD49") (class "Default")
      (node (ref "P6") (pin "32") (pinfunction "32_32") (pintype "passive"))
      (node (ref "U1") (pin "142") (pinfunction "PE1_142") (pintype "bidirectional"))
    )
    (net (code "61") (name "/LD50") (class "Default")
      (node (ref "P6") (pin "34") (pinfunction "34_34") (pintype "passive"))
      (node (ref "U1") (pin "1") (pinfunction "PE2_1") (pintype "bidirectional"))
    )
    (net (code "62") (name "/LD51") (class "Default")
      (node (ref "P6") (pin "36") (pinfunction "36_36") (pintype "passive"))
      (node (ref "U1") (pin "2") (pinfunction "PE3_2") (pintype "bidirectional"))
    )
    (net (code "63") (name "/LD52") (class "Default")
      (node (ref "P7") (pin "3") (pinfunction "3_3") (pintype "passive"))
      (node (ref "U1") (pin "3") (pinfunction "PE4_3") (pintype "bidirectional"))
    )
    (net (code "64") (name "/LD53") (class "Default")
      (node (ref "P7") (pin "5") (pinfunction "5_5") (pintype "passive"))
      (node (ref "U1") (pin "4") (pinfunction "PE5_4") (pintype "bidirectional"))
    )
    (net (code "65") (name "/LD54") (class "Default")
      (node (ref "P7") (pin "7") (pinfunction "7_7") (pintype "passive"))
      (node (ref "U1") (pin "5") (pinfunction "PE6_5") (pintype "bidirectional"))
    )
    (net (code "66") (name "/LD55") (class "Default")
      (node (ref "P7") (pin "9") (pinfunction "9_9") (pintype "passive"))
      (node (ref "U1") (pin "58") (pinfunction "PE7_58") (pintype "bidirectional"))
    )
    (net (code "67") (name "/LD56") (class "Default")
      (node (ref "P7") (pin "11") (pinfunction "11_11") (pintype "passive"))
      (node (ref "U1") (pin "59") (pinfunction "PE8_59") (pintype "bidirectional"))
    )
    (net (code "68") (name "/LD57") (class "Default")
      (node (ref "P7") (pin "13") (pinfunction "13_13") (pintype "passive"))
      (node (ref "U1") (pin "60") (pinfunction "PE9_60") (pintype "bidirectional"))
    )
    (net (code "69") (name "/LD58") (class "Default")
      (node (ref "P7") (pin "15") (pinfunction "15_15") (pintype "passive"))
      (node (ref "U1") (pin "63") (pinfunction "PE10_63") (pintype "bidirectional"))
    )
    (net (code "70") (name "/LD59") (class "Default")
      (node (ref "P7") (pin "17") (pinfunction "17_17") (pintype "passive"))
      (node (ref "U1") (pin "64") (pinfunction "PE11_64") (pintype "bidirectional"))
    )
    (net (code "71") (name "/LD60") (class "Default")
      (node (ref "P7") (pin "19") (pinfunction "19_19") (pintype "passive"))
      (node (ref "U1") (pin "65") (pinfunction "PE12_65") (pintype "bidirectional"))
    )
    (net (code "72") (name "/LD61") (class "Default")
      (node (ref "P7") (pin "21") (pinfunction "21_21") (pintype "passive"))
      (node (ref "U1") (pin "66") (pinfunction "PE13_66") (pintype "bidirectional"))
    )
    (net (code "73") (name "/LD62") (class "Default")
      (node (ref "P7") (pin "23") (pinfunction "23_23") (pintype "passive"))
      (node (ref "U1") (pin "67") (pinfunction "PE14_67") (pintype "bidirectional"))
    )
    (net (code "74") (name "/LD63") (class "Default")
      (node (ref "P7") (pin "25") (pinfunction "25_25") (pintype "passive"))
      (node (ref "U1") (pin "68") (pinfunction "PE15_68") (pintype "bidirectional"))
    )
    (net (code "75") (name "/LD64") (class "Default")
      (node (ref "P7") (pin "27") (pinfunction "27_27") (pintype "passive"))
      (node (ref "U1") (pin "10") (pinfunction "PF0_10") (pintype "bidirectional"))
    )
    (net (code "76") (name "/LD65") (class "Default")
      (node (ref "P7") (pin "29") (pinfunction "29_29") (pintype "passive"))
      (node (ref "U1") (pin "11") (pinfunction "PF1_11") (pintype "bidirectional"))
    )
    (net (code "77") (name "/LD66") (class "Default")
      (node (ref "P7") (pin "31") (pinfunction "31_31") (pintype "passive"))
      (node (ref "U1") (pin "12") (pinfunction "PF2_12") (pintype "bidirectional"))
    )
    (net (code "78") (name "/LD67") (class "Default")
      (node (ref "P7") (pin "33") (pinfunction "33_33") (pintype "passive"))
      (node (ref "U1") (pin "13") (pinfunction "PF3_13") (pintype "bidirectional"))
    )
    (net (code "79") (name "/LD68") (class "Default")
      (node (ref "P7") (pin "35") (pinfunction "35_35") (pintype "passive"))
      (node (ref "U1") (pin "14") (pinfunction "PF4_14") (pintype "bidirectional"))
    )
    (net (code "80") (name "/LD69") (class "Default")
      (node (ref "P7") (pin "37") (pinfunction "37_37") (pintype "passive"))
      (node (ref "U1") (pin "15") (pinfunction "PF5_15") (pintype "bidirectional"))
    )
    (net (code "81") (name "/LD70") (class "Default")
      (node (ref "P7") (pin "4") (pinfunction "4_4") (pintype "passive"))
      (node (ref "U1") (pin "18") (pinfunction "PF6_18") (pintype "bidirectional"))
    )
    (net (code "82") (name "/LD71") (class "Default")
      (node (ref "P7") (pin "6") (pinfunction "6_6") (pintype "passive"))
      (node (ref "U1") (pin "19") (pinfunction "PF7_19") (pintype "bidirectional"))
    )
    (net (code "83") (name "/LD72") (class "Default")
      (node (ref "P7") (pin "8") (pinfunction "8_8") (pintype "passive"))
      (node (ref "U1") (pin "20") (pinfunction "PF8_20") (pintype "bidirectional"))
    )
    (net (code "84") (name "/LD73") (class "Default")
      (node (ref "P7") (pin "10") (pinfunction "10_10") (pintype "passive"))
      (node (ref "U1") (pin "21") (pinfunction "PF9_21") (pintype "bidirectional"))
    )
    (net (code "85") (name "/LD74") (class "Default")
      (node (ref "P7") (pin "12") (pinfunction "12_12") (pintype "passive"))
      (node (ref "U1") (pin "22") (pinfunction "PF10_22") (pintype "bidirectional"))
    )
    (net (code "86") (name "/LD75") (class "Default")
      (node (ref "P7") (pin "14") (pinfunction "14_14") (pintype "passive"))
      (node (ref "U1") (pin "49") (pinfunction "PF11_49") (pintype "bidirectional"))
    )
    (net (code "87") (name "/LD76") (class "Default")
      (node (ref "P7") (pin "16") (pinfunction "16_16") (pintype "passive"))
      (node (ref "U1") (pin "50") (pinfunction "PF12_50") (pintype "bidirectional"))
    )
    (net (code "88") (name "/LD77") (class "Default")
      (node (ref "P7") (pin "18") (pinfunction "18_18") (pintype "passive"))
      (node (ref "U1") (pin "53") (pinfunction "PF13_53") (pintype "bidirectional"))
    )
    (net (code "89") (name "/LD78") (class "Default")
      (node (ref "P7") (pin "20") (pinfunction "20_20") (pintype "passive"))
      (node (ref "U1") (pin "54") (pinfunction "PF14_54") (pintype "bidirectional"))
    )
    (net (code "90") (name "/LD79") (class "Default")
      (node (ref "P7") (pin "22") (pinfunction "22_22") (pintype "passive"))
      (node (ref "U1") (pin "55") (pinfunction "PF15_55") (pintype "bidirectional"))
    )
    (net (code "91") (name "/LD80") (class "Default")
      (node (ref "P7") (pin "24") (pinfunction "24_24") (pintype "passive"))
      (node (ref "U1") (pin "56") (pinfunction "PG0_56") (pintype "bidirectional"))
    )
    (net (code "92") (name "/LD81") (class "Default")
      (node (ref "P7") (pin "26") (pinfunction "26_26") (pintype "passive"))
      (node (ref "U1") (pin "57") (pinfunction "PG1_57") (pintype "bidirectional"))
    )
    (net (code "93") (name "/LD82") (class "Default")
      (node (ref "P7") (pin "28") (pinfunction "28_28") (pintype "passive"))
      (node (ref "U1") (pin "87") (pinfunction "PG2_87") (pintype "bidirectional"))
    )
    (net (code "94") (name "/LD83") (class "Default")
      (node (ref "P7") (pin "30") (pinfunction "30_30") (pintype "passive"))
      (node (ref "U1") (pin "88") (pinfunction "PG3_88") (pintype "bidirectional"))
    )
    (net (code "95") (name "/LD84") (class "Default")
      (node (ref "P7") (pin "32") (pinfunction "32_32") (pintype "passive"))
      (node (ref "U1") (pin "89") (pinfunction "PG4_89") (pintype "bidirectional"))
    )
    (net (code "96") (name "/LD85") (class "Default")
      (node (ref "P7") (pin "34") (pinfunction "34_34") (pintype "passive"))
      (node (ref "U1") (pin "90") (pinfunction "PG5_90") (pintype "bidirectional"))
    )
    (net (code "97") (name "/LD86") (class "Default")
      (node (ref "P7") (pin "36") (pinfunction "36_36") (pintype "passive"))
      (node (ref "U1") (pin "91") (pinfunction "PG6_91") (pintype "bidirectional"))
    )
    (net (code "98") (name "/LD87") (class "Default")
      (node (ref "P7") (pin "38") (pinfunction "38_38") (pintype "passive"))
      (node (ref "U1") (pin "92") (pinfunction "PG7_92") (pintype "bidirectional"))
    )
    (net (code "99") (name "/LD88") (class "Default")
      (node (ref "P7") (pin "40") (pinfunction "40_40") (pintype "passive"))
      (node (ref "U1") (pin "93") (pinfunction "PG8_93") (pintype "bidirectional"))
    )
    (net (code "100") (name "/MCU_RX1") (class "Default")
      (node (ref "D6") (pin "2") (pinfunction "2_2") (pintype "passive"))
      (node (ref "P15") (pin "3") (pinfunction "3_3") (pintype "passive"))
      (node (ref "P17") (pin "6") (pinfunction "6_6") (pintype "passive"))
      (node (ref "P18") (pin "3") (pinfunction "3_3") (pintype "passive"))
      (node (ref "U1") (pin "102") (pinfunction "PA10/USART1_RX_102") (pintype "bidirectional"))
    )
    (net (code "101") (name "/MCU_RX2") (class "Default")
      (node (ref "D4") (pin "2") (pinfunction "2_2") (pintype "passive"))
      (node (ref "P15") (pin "1") (pinfunction "1_1") (pintype "passive"))
      (node (ref "P17") (pin "2") (pinfunction "2_2") (pintype "passive"))
      (node (ref "U1") (pin "37") (pinfunction "PA3_37") (pintype "bidirectional"))
    )
    (net (code "102") (name "/MCU_TX1") (class "Default")
      (node (ref "D5") (pin "2") (pinfunction "2_2") (pintype "passive"))
      (node (ref "P15") (pin "6") (pinfunction "6_6") (pintype "passive"))
      (node (ref "P17") (pin "5") (pinfunction "5_5") (pintype "passive"))
      (node (ref "P18") (pin "4") (pinfunction "4_4") (pintype "passive"))
      (node (ref "U1") (pin "101") (pinfunction "PA9/USART1_TX_101") (pintype "bidirectional"))
    )
    (net (code "103") (name "/MCU_TX2") (class "Default")
      (node (ref "D3") (pin "2") (pinfunction "2_2") (pintype "passive"))
      (node (ref "P15") (pin "4") (pinfunction "4_4") (pintype "passive"))
      (node (ref "P17") (pin "1") (pinfunction "1_1") (pintype "passive"))
      (node (ref "U1") (pin "36") (pinfunction "PA2_36") (pintype "bidirectional"))
    )
    (net (code "104") (name "/PA4") (class "Default")
      (node (ref "U1") (pin "40") (pinfunction "PA4_40") (pintype "bidirectional"))
      (node (ref "U6") (pin "1") (pinfunction "CS_1") (pintype "passive"))
    )
    (net (code "105") (name "/PA5") (class "Default")
      (node (ref "U1") (pin "41") (pinfunction "PA5_41") (pintype "bidirectional"))
      (node (ref "U6") (pin "6") (pinfunction "CLK_6") (pintype "passive"))
    )
    (net (code "106") (name "/PA6") (class "Default")
      (node (ref "U1") (pin "42") (pinfunction "PA6_42") (pintype "bidirectional"))
      (node (ref "U6") (pin "2") (pinfunction "SO_2") (pintype "passive"))
    )
    (net (code "107") (name "/PA7") (class "Default")
      (node (ref "U1") (pin "43") (pinfunction "PA7_43") (pintype "bidirectional"))
      (node (ref "U6") (pin "5") (pinfunction "SI_5") (pintype "passive"))
    )
    (net (code "108") (name "/PA8") (class "Default")
      (node (ref "U1") (pin "100") (pinfunction "PA8_100") (pintype "bidirectional"))
    )
    (net (code "109") (name "/PG9") (class "Default")
      (node (ref "U1") (pin "124") (pinfunction "PG9_124") (pintype "bidirectional"))
    )
    (net (code "110") (name "/PG10") (class "Default")
      (node (ref "U1") (pin "125") (pinfunction "PG10_125") (pintype "bidirectional"))
    )
    (net (code "111") (name "/PG11") (class "Default")
      (node (ref "U1") (pin "126") (pinfunction "PG11_126") (pintype "bidirectional"))
    )
    (net (code "112") (name "/PG12") (class "Default")
      (node (ref "U1") (pin "127") (pinfunction "PG12_127") (pintype "bidirectional"))
    )
    (net (code "113") (name "/PG13") (class "Default")
      (node (ref "U1") (pin "128") (pinfunction "PG13_128") (pintype "bidirectional"))
    )
    (net (code "114") (name "/PG14") (class "Default")
      (node (ref "U1") (pin "129") (pinfunction "PG14_129") (pintype "bidirectional"))
    )
    (net (code "115") (name "/PG15") (class "Default")
      (node (ref "U1") (pin "132") (pinfunction "PG15_132") (pintype "bidirectional"))
    )
    (net (code "116") (name "/RESET") (class "Default")
      (node (ref "C24") (pin "1") (pinfunction "1_1") (pintype "passive"))
      (node (ref "P5") (pin "15") (pinfunction "15_15") (pintype "passive"))
      (node (ref "R10") (pin "1") (pinfunction "1_1") (pintype "passive"))
      (node (ref "RESET1") (pin "1") (pinfunction "1_1") (pintype "passive"))
      (node (ref "U1") (pin "25") (pinfunction "NRST_25") (pintype "bidirectional"))
    )
    (net (code "117") (name "/USB_DN") (class "Default")
      (node (ref "P2") (pin "2") (pinfunction "D-_2") (pintype "passive"))
      (node (ref "U5") (pin "2") (pinfunction "UD-_2") (pintype "passive"))
    )
    (net (code "118") (name "/USB_DP") (class "Default")
      (node (ref "P2") (pin "3") (pinfunction "D+_3") (pintype "passive"))
      (node (ref "U5") (pin "1") (pinfunction "UD+_1") (pintype "passive"))
    )
    (net (code "119") (name "/WIFI_RX") (class "Default")
      (node (ref "P16") (pin "1") (pinfunction "RX_1") (pintype "passive"))
      (node (ref "P17") (pin "3") (pinfunction "3_3") (pintype "passive"))
    )
    (net (code "120") (name "/WIFI_TX") (class "Default")
      (node (ref "P16") (pin "8") (pinfunction "TX_8") (pintype "passive"))
      (node (ref "P17") (pin "4") (pinfunction "4_4") (pintype "passive"))
    )
    (net (code "121") (name "GND") (class "Default")
      (node (ref "C1") (pin "1") (pinfunction "1_1") (pintype "passive"))
      (node (ref "C10") (pin "1") (pinfunction "1_1") (pintype "passive"))
      (node (ref "C11") (pin "1") (pinfunction "1_1") (pintype "passive"))
      (node (ref "C12") (pin "1") (pinfunction "1_1") (pintype "passive"))
      (node (ref "C13") (pin "1") (pinfunction "1_1") (pintype "passive"))
      (node (ref "C14") (pin "1") (pinfunction "1_1") (pintype "passive"))
      (node (ref "C15") (pin "1") (pinfunction "1_1") (pintype "passive"))
      (node (ref "C16") (pin "1") (pinfunction "1_1") (pintype "passive"))
      (node (ref "C17") (pin "1") (pinfunction "1_1") (pintype "passive"))
      (node (ref "C18") (pin "1") (pintype "passive"))
      (node (ref "C19") (pin "1") (pintype "passive"))
      (node (ref "C2") (pin "1") (pinfunction "1_1") (pintype "passive"))
      (node (ref "C20") (pin "1") (pintype "passive"))
      (node (ref "C21") (pin "1") (pinfunction "1_1") (pintype "passive"))
      (node (ref "C22") (pin "1") (pinfunction "1_1") (pintype "passive"))
      (node (ref "C23") (pin "1") (pintype "passive"))
      (node (ref "C24") (pin "2") (pinfunction "2_2") (pintype "passive"))
      (node (ref "C25") (pin "1") (pintype "passive"))
      (node (ref "C26") (pin "1") (pintype "passive"))
      (node (ref "C27") (pin "1") (pintype "passive"))
      (node (ref "C28") (pin "1") (pintype "passive"))
      (node (ref "C3") (pin "1") (pinfunction "1_1") (pintype "passive"))
      (node (ref "C4") (pin "1") (pinfunction "1_1") (pintype "passive"))
      (node (ref "C5") (pin "1") (pinfunction "1_1") (pintype "passive"))
      (node (ref "C6") (pin "1") (pinfunction "1_1") (pintype "passive"))
      (node (ref "C7") (pin "1") (pinfunction "1_1") (pintype "passive"))
      (node (ref "C8") (pin "1") (pinfunction "1_1") (pintype "passive"))
      (node (ref "C9") (pin "1") (pinfunction "1_1") (pintype "passive"))
      (node (ref "D1") (pin "2") (pinfunction "2_2") (pintype "passive"))
      (node (ref "D2") (pin "2") (pinfunction "2_2") (pintype "passive"))
      (node (ref "M19") (pin "1") (pinfunction "1_1") (pintype "passive"))
      (node (ref "M19") (pin "2") (pinfunction "2_2") (pintype "passive"))
      (node (ref "M19") (pin "3") (pinfunction "3_3") (pintype "passive"))
      (node (ref "M19") (pin "4") (pinfunction "4_4") (pintype "passive"))
      (node (ref "M19") (pin "5") (pinfunction "5_5") (pintype "passive"))
      (node (ref "M19") (pin "6") (pinfunction "6_6") (pintype "passive"))
      (node (ref "M19") (pin "7") (pinfunction "7_7") (pintype "passive"))
      (node (ref "M19") (pin "8") (pinfunction "8_8") (pintype "passive"))
      (node (ref "M19") (pin "9") (pinfunction "9_9") (pintype "passive"))
      (node (ref "M20") (pin "1") (pinfunction "1_1") (pintype "passive"))
      (node (ref "M20") (pin "2") (pinfunction "2_2") (pintype "passive"))
      (node (ref "M20") (pin "3") (pinfunction "3_3") (pintype "passive"))
      (node (ref "M20") (pin "4") (pinfunction "4_4") (pintype "passive"))
      (node (ref "M20") (pin "5") (pinfunction "5_5") (pintype "passive"))
      (node (ref "M20") (pin "6") (pinfunction "6_6") (pintype "passive"))
      (node (ref "M20") (pin "7") (pinfunction "7_7") (pintype "passive"))
      (node (ref "M20") (pin "8") (pinfunction "8_8") (pintype "passive"))
      (node (ref "M20") (pin "9") (pinfunction "9_9") (pintype "passive"))
      (node (ref "M21") (pin "1") (pinfunction "1_1") (pintype "passive"))
      (node (ref "M21") (pin "2") (pinfunction "2_2") (pintype "passive"))
      (node (ref "M21") (pin "3") (pinfunction "3_3") (pintype "passive"))
      (node (ref "M21") (pin "4") (pinfunction "4_4") (pintype "passive"))
      (node (ref "M21") (pin "5") (pinfunction "5_5") (pintype "passive"))
      (node (ref "M21") (pin "6") (pinfunction "6_6") (pintype "passive"))
      (node (ref "M21") (pin "7") (pinfunction "7_7") (pintype "passive"))
      (node (ref "M21") (pin "8") (pinfunction "8_8") (pintype "passive"))
      (node (ref "M21") (pin "9") (pinfunction "9_9") (pintype "passive"))
      (node (ref "M22") (pin "1") (pinfunction "1_1") (pintype "passive"))
      (node (ref "M22") (pin "2") (pinfunction "2_2") (pintype "passive"))
      (node (ref "M22") (pin "3") (pinfunction "3_3") (pintype "passive"))
      (node (ref "M22") (pin "4") (pinfunction "4_4") (pintype "passive"))
      (node (ref "M22") (pin "5") (pinfunction "5_5") (pintype "passive"))
      (node (ref "M22") (pin "6") (pinfunction "6_6") (pintype "passive"))
      (node (ref "M22") (pin "7") (pinfunction "7_7") (pintype "passive"))
      (node (ref "M22") (pin "8") (pinfunction "8_8") (pintype "passive"))
      (node (ref "M22") (pin "9") (pinfunction "9_9") (pintype "passive"))
      (node (ref "M23") (pin "1") (pinfunction "1_1") (pintype "passive"))
      (node (ref "M23") (pin "2") (pinfunction "2_2") (pintype "passive"))
      (node (ref "M23") (pin "3") (pinfunction "3_3") (pintype "passive"))
      (node (ref "M23") (pin "4") (pinfunction "4_4") (pintype "passive"))
      (node (ref "M23") (pin "5") (pinfunction "5_5") (pintype "passive"))
      (node (ref "M23") (pin "6") (pinfunction "6_6") (pintype "passive"))
      (node (ref "M23") (pin "7") (pinfunction "7_7") (pintype "passive"))
      (node (ref "M23") (pin "8") (pinfunction "8_8") (pintype "passive"))
      (node (ref "M23") (pin "9") (pinfunction "9_9") (pintype "passive"))
      (node (ref "M24") (pin "1") (pinfunction "1_1") (pintype "passive"))
      (node (ref "M24") (pin "2") (pinfunction "2_2") (pintype "passive"))
      (node (ref "M24") (pin "3") (pinfunction "3_3") (pintype "passive"))
      (node (ref "M24") (pin "4") (pinfunction "4_4") (pintype "passive"))
      (node (ref "M24") (pin "5") (pinfunction "5_5") (pintype "passive"))
      (node (ref "M24") (pin "6") (pinfunction "6_6") (pintype "passive"))
      (node (ref "M24") (pin "7") (pinfunction "7_7") (pintype "passive"))
      (node (ref "M24") (pin "8") (pinfunction "8_8") (pintype "passive"))
      (node (ref "M24") (pin "9") (pinfunction "9_9") (pintype "passive"))
      (node (ref "P1") (pin "3") (pinfunction "3_3") (pintype "passive"))
      (node (ref "P1") (pin "4") (pinfunction "4_4") (pintype "passive"))
      (node (ref "P16") (pin "4") (pinfunction "GND_4") (pintype "passive"))
      (node (ref "P18") (pin "2") (pinfunction "2_2") (pintype "passive"))
      (node (ref "P19") (pin "3") (pinfunction "3_3") (pintype "passive"))
      (node (ref "P2") (pin "5") (pinfunction "GND_5") (pintype "passive"))
      (node (ref "P4") (pin "5") (pinfunction "5_5") (pintype "passive"))
      (node (ref "P4") (pin "6") (pinfunction "6_6") (pintype "passive"))
      (node (ref "P5") (pin "10") (pinfunction "10_10") (pintype "passive"))
      (node (ref "P5") (pin "12") (pinfunction "12_12") (pintype "passive"))
      (node (ref "P5") (pin "14") (pinfunction "14_14") (pintype "passive"))
      (node (ref "P5") (pin "16") (pinfunction "16_16") (pintype "passive"))
      (node (ref "P5") (pin "18") (pinfunction "18_18") (pintype "passive"))
      (node (ref "P5") (pin "20") (pinfunction "20_20") (pintype "passive"))
      (node (ref "P5") (pin "4") (pinfunction "4_4") (pintype "passive"))
      (node (ref "P5") (pin "6") (pinfunction "6_6") (pintype "passive"))
      (node (ref "P5") (pin "8") (pinfunction "8_8") (pintype "passive"))
      (node (ref "P6") (pin "1") (pinfunction "1_1") (pintype "passive"))
      (node (ref "P6") (pin "2") (pinfunction "2_2") (pintype "passive"))
      (node (ref "P6") (pin "3") (pinfunction "3_3") (pintype "passive"))
      (node (ref "P6") (pin "37") (pinfunction "37_37") (pintype "passive"))
      (node (ref "P6") (pin "38") (pinfunction "38_38") (pintype "passive"))
      (node (ref "P6") (pin "39") (pinfunction "39_39") (pintype "passive"))
      (node (ref "P6") (pin "4") (pinfunction "4_4") (pintype "passive"))
      (node (ref "P6") (pin "40") (pinfunction "40_40") (pintype "passive"))
      (node (ref "P7") (pin "1") (pinfunction "1_1") (pintype "passive"))
      (node (ref "P7") (pin "2") (pinfunction "2_2") (pintype "passive"))
      (node (ref "P7") (pin "39") (pinfunction "39_39") (pintype "passive"))
      (node (ref "Q70") (pin "2") (pinfunction "SOURCE_2") (pintype "passive"))
      (node (ref "Q71") (pin "2") (pinfunction "SOURCE_2") (pintype "passive"))
      (node (ref "Q72") (pin "2") (pinfunction "SOURCE_2") (pintype "passive"))
      (node (ref "Q73") (pin "2") (pinfunction "SOURCE_2") (pintype "passive"))
      (node (ref "Q74") (pin "2") (pinfunction "SOURCE_2") (pintype "passive"))
      (node (ref "Q75") (pin "2") (pinfunction "SOURCE_2") (pintype "passive"))
      (node (ref "Q76") (pin "2") (pinfunction "SOURCE_2") (pintype "passive"))
      (node (ref "Q77") (pin "2") (pinfunction "SOURCE_2") (pintype "passive"))
      (node (ref "Q78") (pin "2") (pinfunction "SOURCE_2") (pintype "passive"))
      (node (ref "Q79") (pin "2") (pinfunction "SOURCE_2") (pintype "passive"))
      (node (ref "Q80") (pin "2") (pinfunction "SOURCE_2") (pintype "passive"))
      (node (ref "Q81") (pin "2") (pinfunction "SOURCE_2") (pintype "passive"))
      (node (ref "Q82") (pin "2") (pinfunction "SOURCE_2") (pintype "passive"))
      (node (ref "Q83") (pin "2") (pinfunction "SOURCE_2") (pintype "passive"))
      (node (ref "Q84") (pin "2") (pinfunction "SOURCE_2") (pintype "passive"))
      (node (ref "Q85") (pin "2") (pinfunction "SOURCE_2") (pintype "passive"))
      (node (ref "Q86") (pin "2") (pinfunction "SOURCE_2") (pintype "passive"))
      (node (ref "Q87") (pin "2") (pinfunction "SOURCE_2") (pintype "passive"))
      (node (ref "Q88") (pin "2") (pinfunction "SOURCE_2") (pintype "passive"))
      (node (ref "R13") (pin "1") (pinfunction "1_1") (pintype "passive"))
      (node (ref "R8") (pin "1") (pinfunction "1_1") (pintype "passive"))
      (node (ref "RESET1") (pin "2") (pinfunction "2_2") (pintype "passive"))
      (node (ref "U1") (pin "107") (pinfunction "VSS_2_107") (pintype "power_in"))
      (node (ref "U1") (pin "120") (pinfunction "VSS_10_120") (pintype "power_in"))
      (node (ref "U1") (pin "130") (pinfunction "VSS_11_130") (pintype "power_in"))
      (node (ref "U1") (pin "143") (pinfunction "VSS_3_143") (pintype "power_in"))
      (node (ref "U1") (pin "16") (pinfunction "VSS_5_16") (pintype "power_in"))
      (node (ref "U1") (pin "30") (pinfunction "VSSA_30") (pintype "power_in"))
      (node (ref "U1") (pin "38") (pinfunction "VSS_4_38") (pintype "power_in"))
      (node (ref "U1") (pin "51") (pinfunction "VSS_6_51") (pintype "power_in"))
      (node (ref "U1") (pin "61") (pinfunction "VSS_7_61") (pintype "power_in"))
      (node (ref "U1") (pin "71") (pinfunction "VSS_1_71") (pintype "power_in"))
      (node (ref "U1") (pin "83") (pinfunction "VSS_8_83") (pintype "power_in"))
      (node (ref "U1") (pin "94") (pinfunction "VSS_9_94") (pintype "power_in"))
      (node (ref "U2") (pin "2") (pinfunction "GND_2") (pintype "power_in"))
      (node (ref "U4") (pin "1") (pinfunction "GND_1") (pintype "power_in"))
      (node (ref "U5") (pin "3") (pinfunction "GND_3") (pintype "passive"))
      (node (ref "U6") (pin "4") (pinfunction "GND_4") (pintype "passive"))
    )
    (net (code "122") (name "Net-(D1-Pad1)") (class "Default")
      (node (ref "D1") (pin "1") (pinfunction "1_1") (pintype "passive"))
      (node (ref "R9") (pin "2") (pintype "passive"))
    )
    (net (code "123") (name "Net-(D2-Pad1)") (class "Default")
      (node (ref "D2") (pin "1") (pinfunction "1_1") (pintype "passive"))
      (node (ref "R6") (pin "2") (pintype "passive"))
    )
    (net (code "124") (name "Net-(D3-Pad1)") (class "Default")
      (node (ref "D3") (pin "1") (pinfunction "1_1") (pintype "passive"))
      (node (ref "R194") (pin "2") (pintype "passive"))
    )
    (net (code "125") (name "Net-(D4-Pad1)") (class "Default")
      (node (ref "D4") (pin "1") (pinfunction "1_1") (pintype "passive"))
      (node (ref "R195") (pin "2") (pintype "passive"))
    )
    (net (code "126") (name "Net-(D5-Pad1)") (class "Default")
      (node (ref "D5") (pin "1") (pinfunction "1_1") (pintype "passive"))
      (node (ref "R196") (pin "2") (pintype "passive"))
    )
    (net (code "127") (name "Net-(D6-Pad1)") (class "Default")
      (node (ref "D6") (pin "1") (pinfunction "1_1") (pintype "passive"))
      (node (ref "R197") (pin "2") (pintype "passive"))
    )
    (net (code "128") (name "Net-(LD1-A)") (class "Default")
      (node (ref "LD1") (pin "1") (pinfunction "A_1") (pintype "passive"))
      (node (ref "R18") (pin "1") (pinfunction "1_1") (pintype "passive"))
    )
    (net (code "129") (name "Net-(LD1-K)") (class "Default")
      (node (ref "LD1") (pin "2") (pinfunction "K_2") (pintype "passive"))
      (node (ref "Q70") (pin "3") (pinfunction "DRAIN_3") (pintype "passive"))
    )
    (net (code "130") (name "Net-(LD2-A)") (class "Default")
      (node (ref "LD2") (pin "1") (pinfunction "A_1") (pintype "passive"))
      (node (ref "R20") (pin "1") (pinfunction "1_1") (pintype "passive"))
    )
    (net (code "131") (name "Net-(LD2-K)") (class "Default")
      (node (ref "LD2") (pin "2") (pinfunction "K_2") (pintype "passive"))
      (node (ref "Q71") (pin "3") (pinfunction "DRAIN_3") (pintype "passive"))
    )
    (net (code "132") (name "Net-(LD3-A)") (class "Default")
      (node (ref "LD3") (pin "1") (pinfunction "A_1") (pintype "passive"))
      (node (ref "R22") (pin "1") (pinfunction "1_1") (pintype "passive"))
    )
    (net (code "133") (name "Net-(LD3-K)") (class "Default")
      (node (ref "LD3") (pin "2") (pinfunction "K_2") (pintype "passive"))
      (node (ref "Q72") (pin "3") (pinfunction "DRAIN_3") (pintype "passive"))
    )
    (net (code "134") (name "Net-(LD4-A)") (class "Default")
      (node (ref "LD4") (pin "1") (pinfunction "A_1") (pintype "passive"))
      (node (ref "R24") (pin "1") (pinfunction "1_1") (pintype "passive"))
    )
    (net (code "135") (name "Net-(LD4-K)") (class "Default")
      (node (ref "LD4") (pin "2") (pinfunction "K_2") (pintype "passive"))
      (node (ref "Q73") (pin "3") (pinfunction "DRAIN_3") (pintype "passive"))
    )
    (net (code "136") (name "Net-(LD5-A)") (class "Default")
      (node (ref "LD5") (pin "1") (pinfunction "A_1") (pintype "passive"))
      (node (ref "R26") (pin "1") (pinfunction "1_1") (pintype "passive"))
    )
    (net (code "137") (name "Net-(LD5-K)") (class "Default")
      (node (ref "LD5") (pin "2") (pinfunction "K_2") (pintype "passive"))
      (node (ref "Q74") (pin "3") (pinfunction "DRAIN_3") (pintype "passive"))
    )
    (net (code "138") (name "Net-(LD6-A)") (class "Default")
      (node (ref "LD6") (pin "1") (pinfunction "A_1") (pintype "passive"))
      (node (ref "R28") (pin "1") (pinfunction "1_1") (pintype "passive"))
    )
    (net (code "139") (name "Net-(LD6-K)") (class "Default")
      (node (ref "LD6") (pin "2") (pinfunction "K_2") (pintype "passive"))
      (node (ref "Q75") (pin "3") (pinfunction "DRAIN_3") (pintype "passive"))
    )
    (net (code "140") (name "Net-(LD7-A)") (class "Default")
      (node (ref "LD7") (pin "1") (pinfunction "A_1") (pintype "passive"))
      (node (ref "R30") (pin "1") (pinfunction "1_1") (pintype "passive"))
    )
    (net (code "141") (name "Net-(LD7-K)") (class "Default")
      (node (ref "LD7") (pin "2") (pinfunction "K_2") (pintype "passive"))
      (node (ref "Q76") (pin "3") (pinfunction "DRAIN_3") (pintype "passive"))
    )
    (net (code "142") (name "Net-(LD8-A)") (class "Default")
      (node (ref "LD8") (pin "1") (pinfunction "A_1") (pintype "passive"))
      (node (ref "R32") (pin "1") (pinfunction "1_1") (pintype "passive"))
    )
    (net (code "143") (name "Net-(LD8-K)") (class "Default")
      (node (ref "LD8") (pin "2") (pinfunction "K_2") (pintype "passive"))
      (node (ref "Q77") (pin "3") (pinfunction "DRAIN_3") (pintype "passive"))
    )
    (net (code "144") (name "Net-(LD9-A)") (class "Default")
      (node (ref "LD9") (pin "1") (pinfunction "A_1") (pintype "passive"))
      (node (ref "R34") (pin "1") (pinfunction "1_1") (pintype "passive"))
    )
    (net (code "145") (name "Net-(LD9-K)") (class "Default")
      (node (ref "LD9") (pin "2") (pinfunction "K_2") (pintype "passive"))
      (node (ref "Q78") (pin "3") (pinfunction "DRAIN_3") (pintype "passive"))
    )
    (net (code "146") (name "Net-(LD10-A)") (class "Default")
      (node (ref "LD10") (pin "1") (pinfunction "A_1") (pintype "passive"))
      (node (ref "R36") (pin "1") (pinfunction "1_1") (pintype "passive"))
    )
    (net (code "147") (name "Net-(LD10-K)") (class "Default")
      (node (ref "LD10") (pin "2") (pinfunction "K_2") (pintype "passive"))
      (node (ref "Q79") (pin "3") (pinfunction "DRAIN_3") (pintype "passive"))
    )
    (net (code "148") (name "Net-(LD11-A)") (class "Default")
      (node (ref "LD11") (pin "1") (pinfunction "A_1") (pintype "passive"))
      (node (ref "R38") (pin "1") (pinfunction "1_1") (pintype "passive"))
    )
    (net (code "149") (name "Net-(LD11-K)") (class "Default")
      (node (ref "LD11") (pin "2") (pinfunction "K_2") (pintype "passive"))
      (node (ref "Q80") (pin "3") (pinfunction "DRAIN_3") (pintype "passive"))
    )
    (net (code "150") (name "Net-(LD12-A)") (class "Default")
      (node (ref "LD12") (pin "1") (pinfunction "A_1") (pintype "passive"))
      (node (ref "R40") (pin "1") (pinfunction "1_1") (pintype "passive"))
    )
    (net (code "151") (name "Net-(LD12-K)") (class "Default")
      (node (ref "LD12") (pin "2") (pinfunction "K_2") (pintype "passive"))
      (node (ref "Q81") (pin "3") (pinfunction "DRAIN_3") (pintype "passive"))
    )
    (net (code "152") (name "Net-(LD13-A)") (class "Default")
      (node (ref "LD13") (pin "1") (pinfunction "A_1") (pintype "passive"))
      (node (ref "R42") (pin "1") (pinfunction "1_1") (pintype "passive"))
    )
    (net (code "153") (name "Net-(LD13-K)") (class "Default")
      (node (ref "LD13") (pin "2") (pinfunction "K_2") (pintype "passive"))
      (node (ref "Q82") (pin "3") (pinfunction "DRAIN_3") (pintype "passive"))
    )
    (net (code "154") (name "Net-(LD14-A)") (class "Default")
      (node (ref "LD14") (pin "1") (pinfunction "A_1") (pintype "passive"))
      (node (ref "R44") (pin "1") (pinfunction "1_1") (pintype "passive"))
    )
    (net (code "155") (name "Net-(LD14-K)") (class "Default")
      (node (ref "LD14") (pin "2") (pinfunction "K_2") (pintype "passive"))
      (node (ref "Q83") (pin "3") (pinfunction "DRAIN_3") (pintype "passive"))
    )
    (net (code "156") (name "Net-(LD15-A)") (class "Default")
      (node (ref "LD15") (pin "1") (pinfunction "A_1") (pintype "passive"))
      (node (ref "R46") (pin "1") (pinfunction "1_1") (pintype "passive"))
    )
    (net (code "157") (name "Net-(LD15-K)") (class "Default")
      (node (ref "LD15") (pin "2") (pinfunction "K_2") (pintype "passive"))
      (node (ref "Q84") (pin "3") (pinfunction "DRAIN_3") (pintype "passive"))
    )
    (net (code "158") (name "Net-(LD16-A)") (class "Default")
      (node (ref "LD16") (pin "1") (pinfunction "A_1") (pintype "passive"))
      (node (ref "R48") (pin "1") (pinfunction "1_1") (pintype "passive"))
    )
    (net (code "159") (name "Net-(LD16-K)") (class "Default")
      (node (ref "LD16") (pin "2") (pinfunction "K_2") (pintype "passive"))
      (node (ref "Q85") (pin "3") (pinfunction "DRAIN_3") (pintype "passive"))
    )
    (net (code "160") (name "Net-(LD17-A)") (class "Default")
      (node (ref "LD17") (pin "1") (pinfunction "A_1") (pintype "passive"))
      (node (ref "R50") (pin "1") (pinfunction "1_1") (pintype "passive"))
    )
    (net (code "161") (name "Net-(LD17-K)") (class "Default")
      (node (ref "LD17") (pin "2") (pinfunction "K_2") (pintype "passive"))
      (node (ref "Q86") (pin "3") (pinfunction "DRAIN_3") (pintype "passive"))
    )
    (net (code "162") (name "Net-(LD18-A)") (class "Default")
      (node (ref "LD18") (pin "1") (pinfunction "A_1") (pintype "passive"))
      (node (ref "R52") (pin "1") (pinfunction "1_1") (pintype "passive"))
    )
    (net (code "163") (name "Net-(LD18-K)") (class "Default")
      (node (ref "LD18") (pin "2") (pinfunction "K_2") (pintype "passive"))
      (node (ref "Q87") (pin "3") (pinfunction "DRAIN_3") (pintype "passive"))
    )
    (net (code "164") (name "Net-(LD19-A)") (class "Default")
      (node (ref "LD19") (pin "1") (pinfunction "A_1") (pintype "passive"))
      (node (ref "R54") (pin "1") (pinfunction "1_1") (pintype "passive"))
    )
    (net (code "165") (name "Net-(LD19-K)") (class "Default")
      (node (ref "LD19") (pin "2") (pinfunction "K_2") (pintype "passive"))
      (node (ref "Q88") (pin "3") (pinfunction "DRAIN_3") (pintype "passive"))
    )
    (net (code "166") (name "Net-(P4-Pad3)") (class "Default")
      (node (ref "P4") (pin "3") (pinfunction "3_3") (pintype "passive"))
      (node (ref "R11") (pin "2") (pinfunction "2_2") (pintype "passive"))
    )
    (net (code "167") (name "Net-(P4-Pad4)") (class "Default")
      (node (ref "P4") (pin "4") (pinfunction "4_4") (pintype "passive"))
      (node (ref "R12") (pin "1") (pinfunction "1_1") (pintype "passive"))
    )
    (net (code "168") (name "Net-(Q70-GATE)") (class "Default")
      (node (ref "Q70") (pin "1") (pinfunction "GATE_1") (pintype "passive"))
      (node (ref "R19") (pin "1") (pinfunction "1_1") (pintype "passive"))
    )
    (net (code "169") (name "Net-(Q71-GATE)") (class "Default")
      (node (ref "Q71") (pin "1") (pinfunction "GATE_1") (pintype "passive"))
      (node (ref "R21") (pin "1") (pinfunction "1_1") (pintype "passive"))
    )
    (net (code "170") (name "Net-(Q72-GATE)") (class "Default")
      (node (ref "Q72") (pin "1") (pinfunction "GATE_1") (pintype "passive"))
      (node (ref "R23") (pin "1") (pinfunction "1_1") (pintype "passive"))
    )
    (net (code "171") (name "Net-(Q73-GATE)") (class "Default")
      (node (ref "Q73") (pin "1") (pinfunction "GATE_1") (pintype "passive"))
      (node (ref "R25") (pin "1") (pinfunction "1_1") (pintype "passive"))
    )
    (net (code "172") (name "Net-(Q74-GATE)") (class "Default")
      (node (ref "Q74") (pin "1") (pinfunction "GATE_1") (pintype "passive"))
      (node (ref "R27") (pin "1") (pinfunction "1_1") (pintype "passive"))
    )
    (net (code "173") (name "Net-(Q75-GATE)") (class "Default")
      (node (ref "Q75") (pin "1") (pinfunction "GATE_1") (pintype "passive"))
      (node (ref "R29") (pin "1") (pinfunction "1_1") (pintype "passive"))
    )
    (net (code "174") (name "Net-(Q76-GATE)") (class "Default")
      (node (ref "Q76") (pin "1") (pinfunction "GATE_1") (pintype "passive"))
      (node (ref "R31") (pin "1") (pinfunction "1_1") (pintype "passive"))
    )
    (net (code "175") (name "Net-(Q77-GATE)") (class "Default")
      (node (ref "Q77") (pin "1") (pinfunction "GATE_1") (pintype "passive"))
      (node (ref "R33") (pin "1") (pinfunction "1_1") (pintype "passive"))
    )
    (net (code "176") (name "Net-(Q78-GATE)") (class "Default")
      (node (ref "Q78") (pin "1") (pinfunction "GATE_1") (pintype "passive"))
      (node (ref "R35") (pin "1") (pinfunction "1_1") (pintype "passive"))
    )
    (net (code "177") (name "Net-(Q79-GATE)") (class "Default")
      (node (ref "Q79") (pin "1") (pinfunction "GATE_1") (pintype "passive"))
      (node (ref "R37") (pin "1") (pinfunction "1_1") (pintype "passive"))
    )
    (net (code "178") (name "Net-(Q80-GATE)") (class "Default")
      (node (ref "Q80") (pin "1") (pinfunction "GATE_1") (pintype "passive"))
      (node (ref "R39") (pin "1") (pinfunction "1_1") (pintype "passive"))
    )
    (net (code "179") (name "Net-(Q81-GATE)") (class "Default")
      (node (ref "Q81") (pin "1") (pinfunction "GATE_1") (pintype "passive"))
      (node (ref "R41") (pin "1") (pinfunction "1_1") (pintype "passive"))
    )
    (net (code "180") (name "Net-(Q82-GATE)") (class "Default")
      (node (ref "Q82") (pin "1") (pinfunction "GATE_1") (pintype "passive"))
      (node (ref "R43") (pin "1") (pinfunction "1_1") (pintype "passive"))
    )
    (net (code "181") (name "Net-(Q83-GATE)") (class "Default")
      (node (ref "Q83") (pin "1") (pinfunction "GATE_1") (pintype "passive"))
      (node (ref "R45") (pin "1") (pinfunction "1_1") (pintype "passive"))
    )
    (net (code "182") (name "Net-(Q84-GATE)") (class "Default")
      (node (ref "Q84") (pin "1") (pinfunction "GATE_1") (pintype "passive"))
      (node (ref "R47") (pin "1") (pinfunction "1_1") (pintype "passive"))
    )
    (net (code "183") (name "Net-(Q85-GATE)") (class "Default")
      (node (ref "Q85") (pin "1") (pinfunction "GATE_1") (pintype "passive"))
      (node (ref "R49") (pin "1") (pinfunction "1_1") (pintype "passive"))
    )
    (net (code "184") (name "Net-(Q86-GATE)") (class "Default")
      (node (ref "Q86") (pin "1") (pinfunction "GATE_1") (pintype "passive"))
      (node (ref "R51") (pin "1") (pinfunction "1_1") (pintype "passive"))
    )
    (net (code "185") (name "Net-(Q87-GATE)") (class "Default")
      (node (ref "Q87") (pin "1") (pinfunction "GATE_1") (pintype "passive"))
      (node (ref "R53") (pin "1") (pinfunction "1_1") (pintype "passive"))
    )
    (net (code "186") (name "Net-(Q88-GATE)") (class "Default")
      (node (ref "Q88") (pin "1") (pinfunction "GATE_1") (pintype "passive"))
      (node (ref "R55") (pin "1") (pinfunction "1_1") (pintype "passive"))
    )
    (net (code "187") (name "Net-(U1A-PC14-OSC32_IN)") (class "Default")
      (node (ref "C16") (pin "2") (pinfunction "2_2") (pintype "passive"))
      (node (ref "U1") (pin "8") (pinfunction "PC14-OSC32_IN_8") (pintype "bidirectional"))
      (node (ref "Y2") (pin "1") (pinfunction "OSC1_1") (pintype "passive"))
    )
    (net (code "188") (name "Net-(U1A-PC15-OSC32_OUT)") (class "Default")
      (node (ref "C17") (pin "2") (pinfunction "2_2") (pintype "passive"))
      (node (ref "U1") (pin "9") (pinfunction "PC15-OSC32_OUT_9") (pintype "bidirectional"))
      (node (ref "Y2") (pin "2") (pinfunction "OSC2_2") (pintype "passive"))
    )
    (net (code "189") (name "Net-(U1B-OSC_IN)") (class "Default")
      (node (ref "C4") (pin "2") (pinfunction "2_2") (pintype "passive"))
      (node (ref "R139") (pin "2") (pinfunction "2_2") (pintype "passive"))
      (node (ref "U1") (pin "23") (pinfunction "OSC_IN_23") (pintype "input"))
      (node (ref "Y1") (pin "2") (pinfunction "OSC2_2") (pintype "passive"))
    )
    (net (code "190") (name "Net-(U1B-OSC_OUT)") (class "Default")
      (node (ref "C3") (pin "2") (pinfunction "2_2") (pintype "passive"))
      (node (ref "R139") (pin "1") (pinfunction "1_1") (pintype "passive"))
      (node (ref "U1") (pin "24") (pinfunction "OSC_OUT_24") (pintype "passive"))
      (node (ref "Y1") (pin "1") (pinfunction "OSC1_1") (pintype "passive"))
    )
    (net (code "191") (name "Net-(U2-BP{slash}FB)") (class "Default")
      (node (ref "R7") (pin "1") (pinfunction "1_1") (pintype "passive"))
      (node (ref "R8") (pin "2") (pinfunction "2_2") (pintype "passive"))
      (node (ref "U2") (pin "4") (pinfunction "BP/FB_4") (pintype "passive"))
    )
    (net (code "192") (name "Net-(U5-RXD)") (class "Default")
      (node (ref "R2") (pin "2") (pintype "passive"))
      (node (ref "U5") (pin "9") (pinfunction "RXD_9") (pintype "passive"))
    )
    (net (code "193") (name "Net-(U5-TXD)") (class "Default")
      (node (ref "R3") (pin "2") (pintype "passive"))
      (node (ref "U5") (pin "8") (pinfunction "TXD_8") (pintype "passive"))
    )
    (net (code "194") (name "Net-(U5-V3)") (class "Default")
      (node (ref "C25") (pin "2") (pintype "passive"))
      (node (ref "U5") (pin "10") (pinfunction "V3_10") (pintype "passive"))
    )
    (net (code "195") (name "Net-(U6-HOLD)") (class "Default")
      (node (ref "R5") (pin "1") (pintype "passive"))
      (node (ref "U6") (pin "7") (pinfunction "HOLD_7") (pintype "passive"))
    )
    (net (code "196") (name "Net-(U6-WP#)") (class "Default")
      (node (ref "R4") (pin "2") (pintype "passive"))
      (node (ref "U6") (pin "3") (pinfunction "WP#_3") (pintype "passive"))
    )
    (net (code "197") (name "USB5V") (class "Default")
      (node (ref "P2") (pin "1") (pinfunction "VCC_1") (pintype "passive"))
      (node (ref "R1") (pin "2") (pintype "passive"))
    )
    (net (code "198") (name "VCC") (class "Default")
      (node (ref "C21") (pin "2") (pinfunction "2_2") (pintype "passive"))
      (node (ref "C26") (pin "2") (pintype "passive"))
      (node (ref "C27") (pin "2") (pintype "passive"))
      (node (ref "R1") (pin "1") (pintype "passive"))
      (node (ref "U4") (pin "3") (pinfunction "IN_3") (pintype "power_in"))
      (node (ref "U5") (pin "7") (pinfunction "VCC_7") (pintype "passive"))
    )
    (net (code "199") (name "VCC2.5") (class "Default")
      (node (ref "C18") (pin "2") (pintype "passive"))
      (node (ref "C20") (pin "2") (pintype "passive"))
      (node (ref "P1") (pin "1") (pinfunction "1_1") (pintype "passive"))
      (node (ref "P1") (pin "2") (pinfunction "2_2") (pintype "passive"))
      (node (ref "R18") (pin "2") (pinfunction "2_2") (pintype "passive"))
      (node (ref "R20") (pin "2") (pinfunction "2_2") (pintype "passive"))
      (node (ref "R22") (pin "2") (pinfunction "2_2") (pintype "passive"))
      (node (ref "R24") (pin "2") (pinfunction "2_2") (pintype "passive"))
      (node (ref "R26") (pin "2") (pinfunction "2_2") (pintype "passive"))
      (node (ref "R28") (pin "2") (pinfunction "2_2") (pintype "passive"))
      (node (ref "R30") (pin "2") (pinfunction "2_2") (pintype "passive"))
      (node (ref "R32") (pin "2") (pinfunction "2_2") (pintype "passive"))
      (node (ref "R34") (pin "2") (pinfunction "2_2") (pintype "passive"))
      (node (ref "R36") (pin "2") (pinfunction "2_2") (pintype "passive"))
      (node (ref "R38") (pin "2") (pinfunction "2_2") (pintype "passive"))
      (node (ref "R40") (pin "2") (pinfunction "2_2") (pintype "passive"))
      (node (ref "R42") (pin "2") (pinfunction "2_2") (pintype "passive"))
      (node (ref "R44") (pin "2") (pinfunction "2_2") (pintype "passive"))
      (node (ref "R46") (pin "2") (pinfunction "2_2") (pintype "passive"))
      (node (ref "R48") (pin "2") (pinfunction "2_2") (pintype "passive"))
      (node (ref "R50") (pin "2") (pinfunction "2_2") (pintype "passive"))
      (node (ref "R52") (pin "2") (pinfunction "2_2") (pintype "passive"))
      (node (ref "R54") (pin "2") (pinfunction "2_2") (pintype "passive"))
      (node (ref "R7") (pin "2") (pinfunction "2_2") (pintype "passive"))
      (node (ref "R9") (pin "1") (pintype "passive"))
      (node (ref "U2") (pin "5") (pinfunction "OUT_5") (pintype "passive"))
    )
    (net (code "200") (name "VCC3.3") (class "Default")
      (node (ref "C19") (pin "2") (pintype "passive"))
      (node (ref "C22") (pin "2") (pinfunction "2_2") (pintype "passive"))
      (node (ref "C23") (pin "2") (pintype "passive"))
      (node (ref "P16") (pin "5") (pinfunction "VDD_5") (pintype "passive"))
      (node (ref "P18") (pin "1") (pinfunction "1_1") (pintype "passive"))
      (node (ref "P19") (pin "4") (pinfunction "4_4") (pintype "passive"))
      (node (ref "P4") (pin "1") (pinfunction "1_1") (pintype "passive"))
      (node (ref "P4") (pin "2") (pinfunction "2_2") (pintype "passive"))
      (node (ref "P5") (pin "1") (pinfunction "1_1") (pintype "passive"))
      (node (ref "P5") (pin "2") (pinfunction "2_2") (pintype "passive"))
      (node (ref "R10") (pin "2") (pinfunction "2_2") (pintype "passive"))
      (node (ref "R14") (pin "1") (pinfunction "1_1") (pintype "passive"))
      (node (ref "R140") (pin "1") (pinfunction "1_1") (pintype "passive"))
      (node (ref "R146") (pin "1") (pinfunction "1_1") (pintype "passive"))
      (node (ref "R15") (pin "1") (pinfunction "1_1") (pintype "passive"))
      (node (ref "R16") (pin "1") (pinfunction "1_1") (pintype "passive"))
      (node (ref "R17") (pin "1") (pinfunction "1_1") (pintype "passive"))
      (node (ref "R194") (pin "1") (pintype "passive"))
      (node (ref "R195") (pin "1") (pintype "passive"))
      (node (ref "R196") (pin "1") (pintype "passive"))
      (node (ref "R197") (pin "1") (pintype "passive"))
      (node (ref "R6") (pin "1") (pintype "passive"))
      (node (ref "U2") (pin "1") (pinfunction "IN_1") (pintype "passive"))
      (node (ref "U2") (pin "3") (pinfunction "EN_3") (pintype "passive"))
      (node (ref "U4") (pin "2") (pinfunction "OUT_2") (pintype "power_in"))
      (node (ref "U4") (pin "4") (pinfunction "OUT_4") (pintype "power_in"))
    )
    (net (code "201") (name "VCC3.3M") (class "Default")
      (node (ref "C10") (pin "2") (pinfunction "2_2") (pintype "passive"))
      (node (ref "C11") (pin "2") (pinfunction "2_2") (pintype "passive"))
      (node (ref "C12") (pin "2") (pinfunction "2_2") (pintype "passive"))
      (node (ref "C13") (pin "2") (pinfunction "2_2") (pintype "passive"))
      (node (ref "C14") (pin "2") (pinfunction "2_2") (pintype "passive"))
      (node (ref "C15") (pin "2") (pinfunction "2_2") (pintype "passive"))
      (node (ref "C5") (pin "2") (pinfunction "2_2") (pintype "passive"))
      (node (ref "C6") (pin "2") (pinfunction "2_2") (pintype "passive"))
      (node (ref "C7") (pin "2") (pinfunction "2_2") (pintype "passive"))
      (node (ref "C8") (pin "2") (pinfunction "2_2") (pintype "passive"))
      (node (ref "C9") (pin "2") (pinfunction "2_2") (pintype "passive"))
      (node (ref "R146") (pin "2") (pinfunction "2_2") (pintype "passive"))
      (node (ref "U1") (pin "108") (pinfunction "VDD_2_108") (pintype "power_in"))
      (node (ref "U1") (pin "121") (pinfunction "VDD_10_121") (pintype "power_in"))
      (node (ref "U1") (pin "131") (pinfunction "VDD_11_131") (pintype "power_in"))
      (node (ref "U1") (pin "144") (pinfunction "VDD_3_144") (pintype "power_in"))
      (node (ref "U1") (pin "17") (pinfunction "VDD_5_17") (pintype "power_in"))
      (node (ref "U1") (pin "39") (pinfunction "VDD_4_39") (pintype "power_in"))
      (node (ref "U1") (pin "52") (pinfunction "VDD_6_52") (pintype "power_in"))
      (node (ref "U1") (pin "62") (pinfunction "VDD_7_62") (pintype "power_in"))
      (node (ref "U1") (pin "72") (pinfunction "VDD_1_72") (pintype "power_in"))
      (node (ref "U1") (pin "84") (pinfunction "VDD_8_84") (pintype "power_in"))
      (node (ref "U1") (pin "95") (pinfunction "VDD_9_95") (pintype "power_in"))
    )
    (net (code "202") (name "VCC_3.3") (class "Default")
      (node (ref "C28") (pin "2") (pintype "passive"))
      (node (ref "R4") (pin "1") (pintype "passive"))
      (node (ref "R5") (pin "2") (pintype "passive"))
      (node (ref "U6") (pin "8") (pinfunction "VCC_8") (pintype "passive"))
    )
    (net (code "203") (name "VDDA") (class "Default")
      (node (ref "C1") (pin "2") (pinfunction "2_2") (pintype "passive"))
      (node (ref "C2") (pin "2") (pinfunction "2_2") (pintype "passive"))
      (node (ref "R140") (pin "2") (pinfunction "2_2") (pintype "passive"))
      (node (ref "U1") (pin "33") (pinfunction "VDDA_33") (pintype "power_in"))
    )
    (net (code "204") (name "unconnected-(P2-NC-Pad4)") (class "Default")
      (node (ref "P2") (pin "4") (pinfunction "NC_4") (pintype "passive"))
    )
    (net (code "205") (name "unconnected-(P5-Pad11)") (class "Default")
      (node (ref "P5") (pin "11") (pinfunction "11_11") (pintype "passive"))
    )
    (net (code "206") (name "unconnected-(P5-Pad17)") (class "Default")
      (node (ref "P5") (pin "17") (pinfunction "17_17") (pintype "passive"))
    )
    (net (code "207") (name "unconnected-(P5-Pad19)") (class "Default")
      (node (ref "P5") (pin "19") (pinfunction "19_19") (pintype "passive"))
    )
    (net (code "208") (name "unconnected-(P16-IO0-Pad2)") (class "Default")
      (node (ref "P16") (pin "2") (pinfunction "IO0_2") (pintype "passive"))
    )
    (net (code "209") (name "unconnected-(P16-IO2-Pad3)") (class "Default")
      (node (ref "P16") (pin "3") (pinfunction "IO2_3") (pintype "passive"))
    )
    (net (code "210") (name "unconnected-(U1B-NC-Pad106)") (class "Default")
      (node (ref "U1") (pin "106") (pinfunction "NC_106") (pintype "passive"))
    )
    (net (code "211") (name "unconnected-(U1C-VBAT-Pad6)") (class "Default")
      (node (ref "U1") (pin "6") (pinfunction "VBAT_6") (pintype "power_in"))
    )
    (net (code "212") (name "unconnected-(U1C-VREF+-Pad32)") (class "Default")
      (node (ref "U1") (pin "32") (pinfunction "VREF+_32") (pintype "power_in"))
    )
    (net (code "213") (name "unconnected-(U1C-VREF--Pad31)") (class "Default")
      (node (ref "U1") (pin "31") (pinfunction "VREF-_31") (pintype "power_in"))
    )
    (net (code "214") (name "unconnected-(U5-CTS#-Pad5)") (class "Default")
      (node (ref "U5") (pin "5") (pinfunction "CTS#_5") (pintype "passive"))
    )
    (net (code "215") (name "unconnected-(U5-RTS#-Pad4)") (class "Default")
      (node (ref "U5") (pin "4") (pinfunction "RTS#_4") (pintype "passive"))
    )
    (net (code "216") (name "unconnected-(U5-TNOW-Pad6)") (class "Default")
      (node (ref "U5") (pin "6") (pinfunction "TNOW_6") (pintype "passive"))
    )
  )
)
